# rev0_1_parts_placement.net
KiCad netlist of a schematic drawn in EAGLE
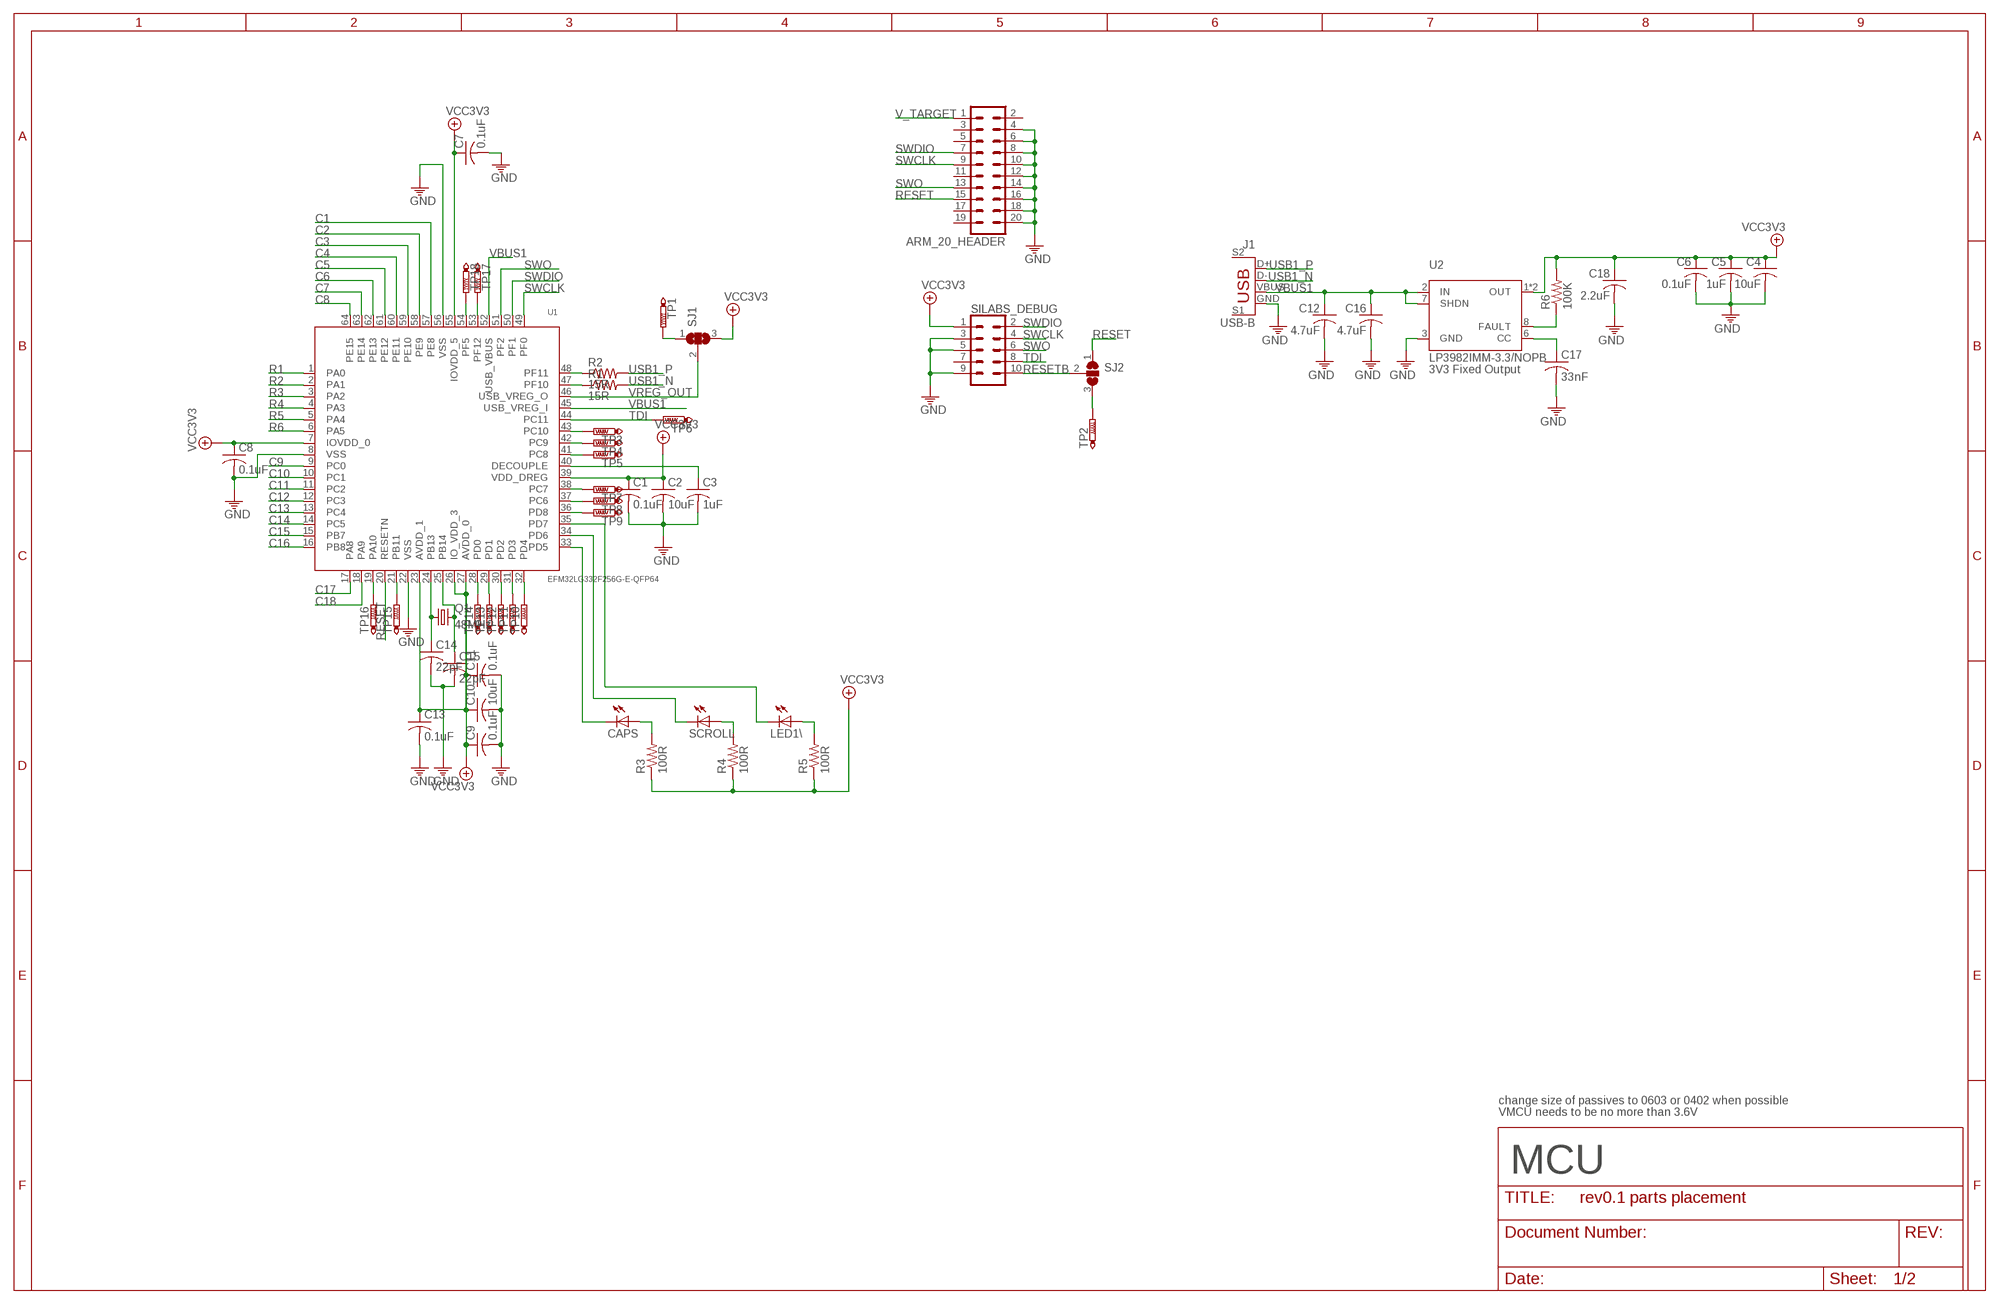
[diagram p0: schematic, sheet 1]
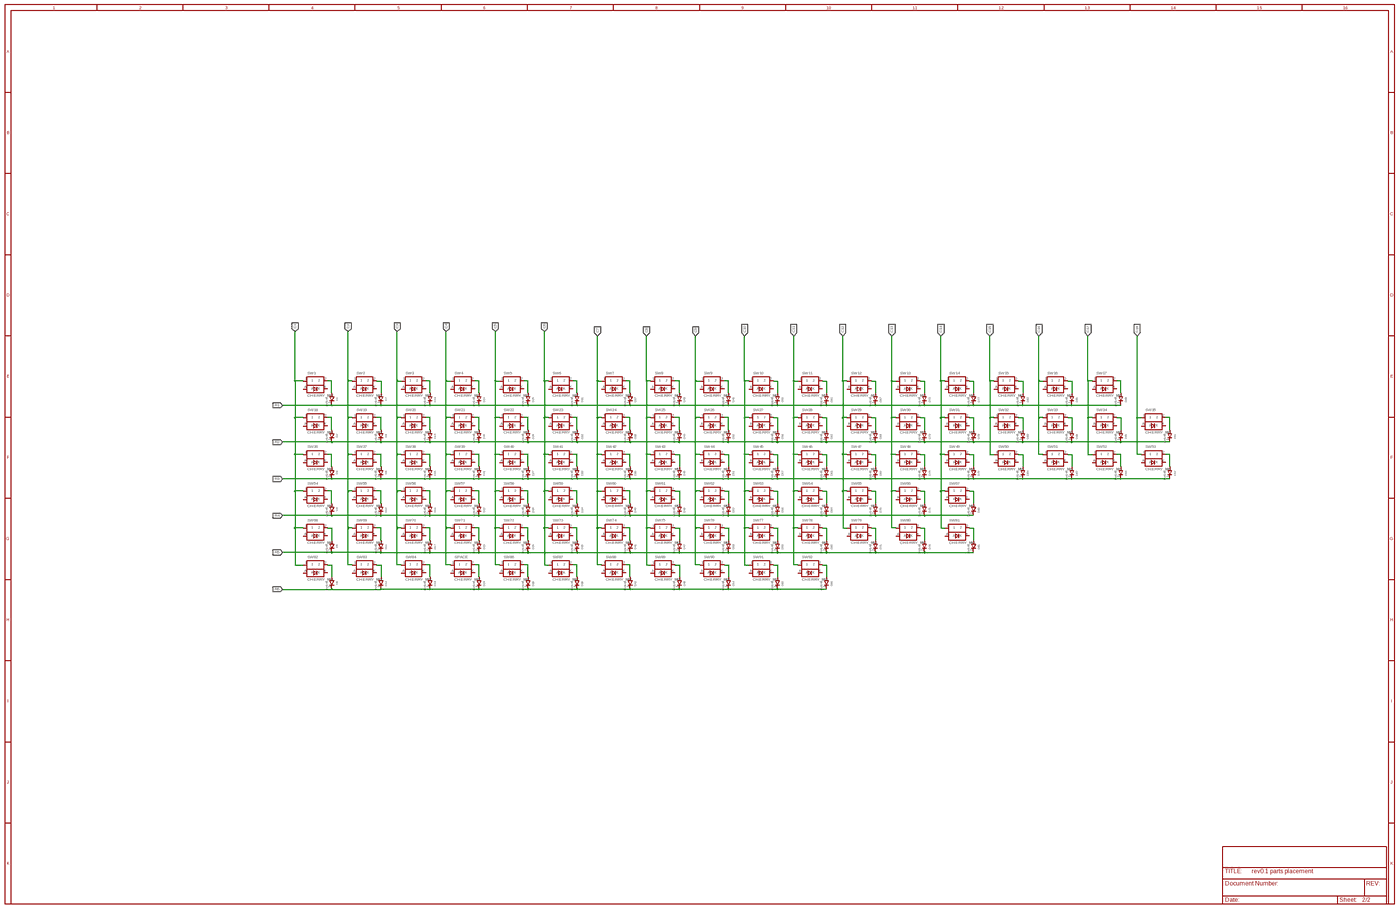
[diagram p1: schematic, sheet 2, overview]
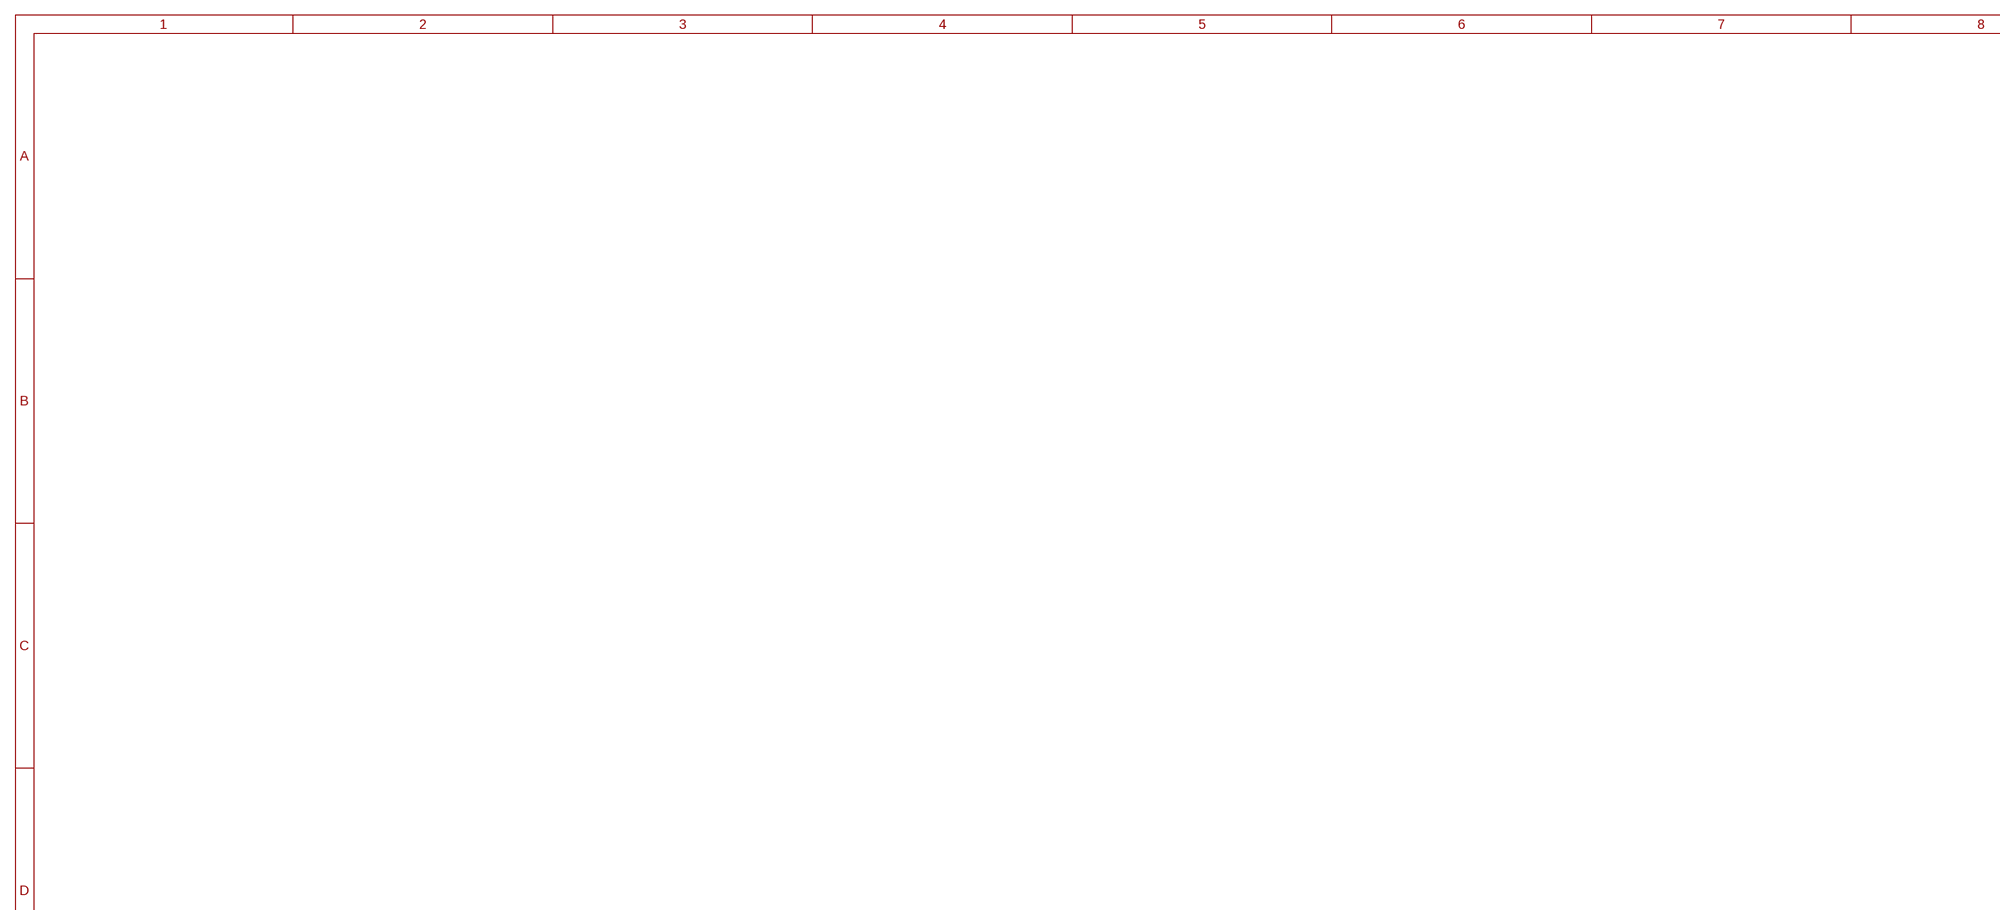
[diagram p2: schematic, sheet 2, part 1 of 4]
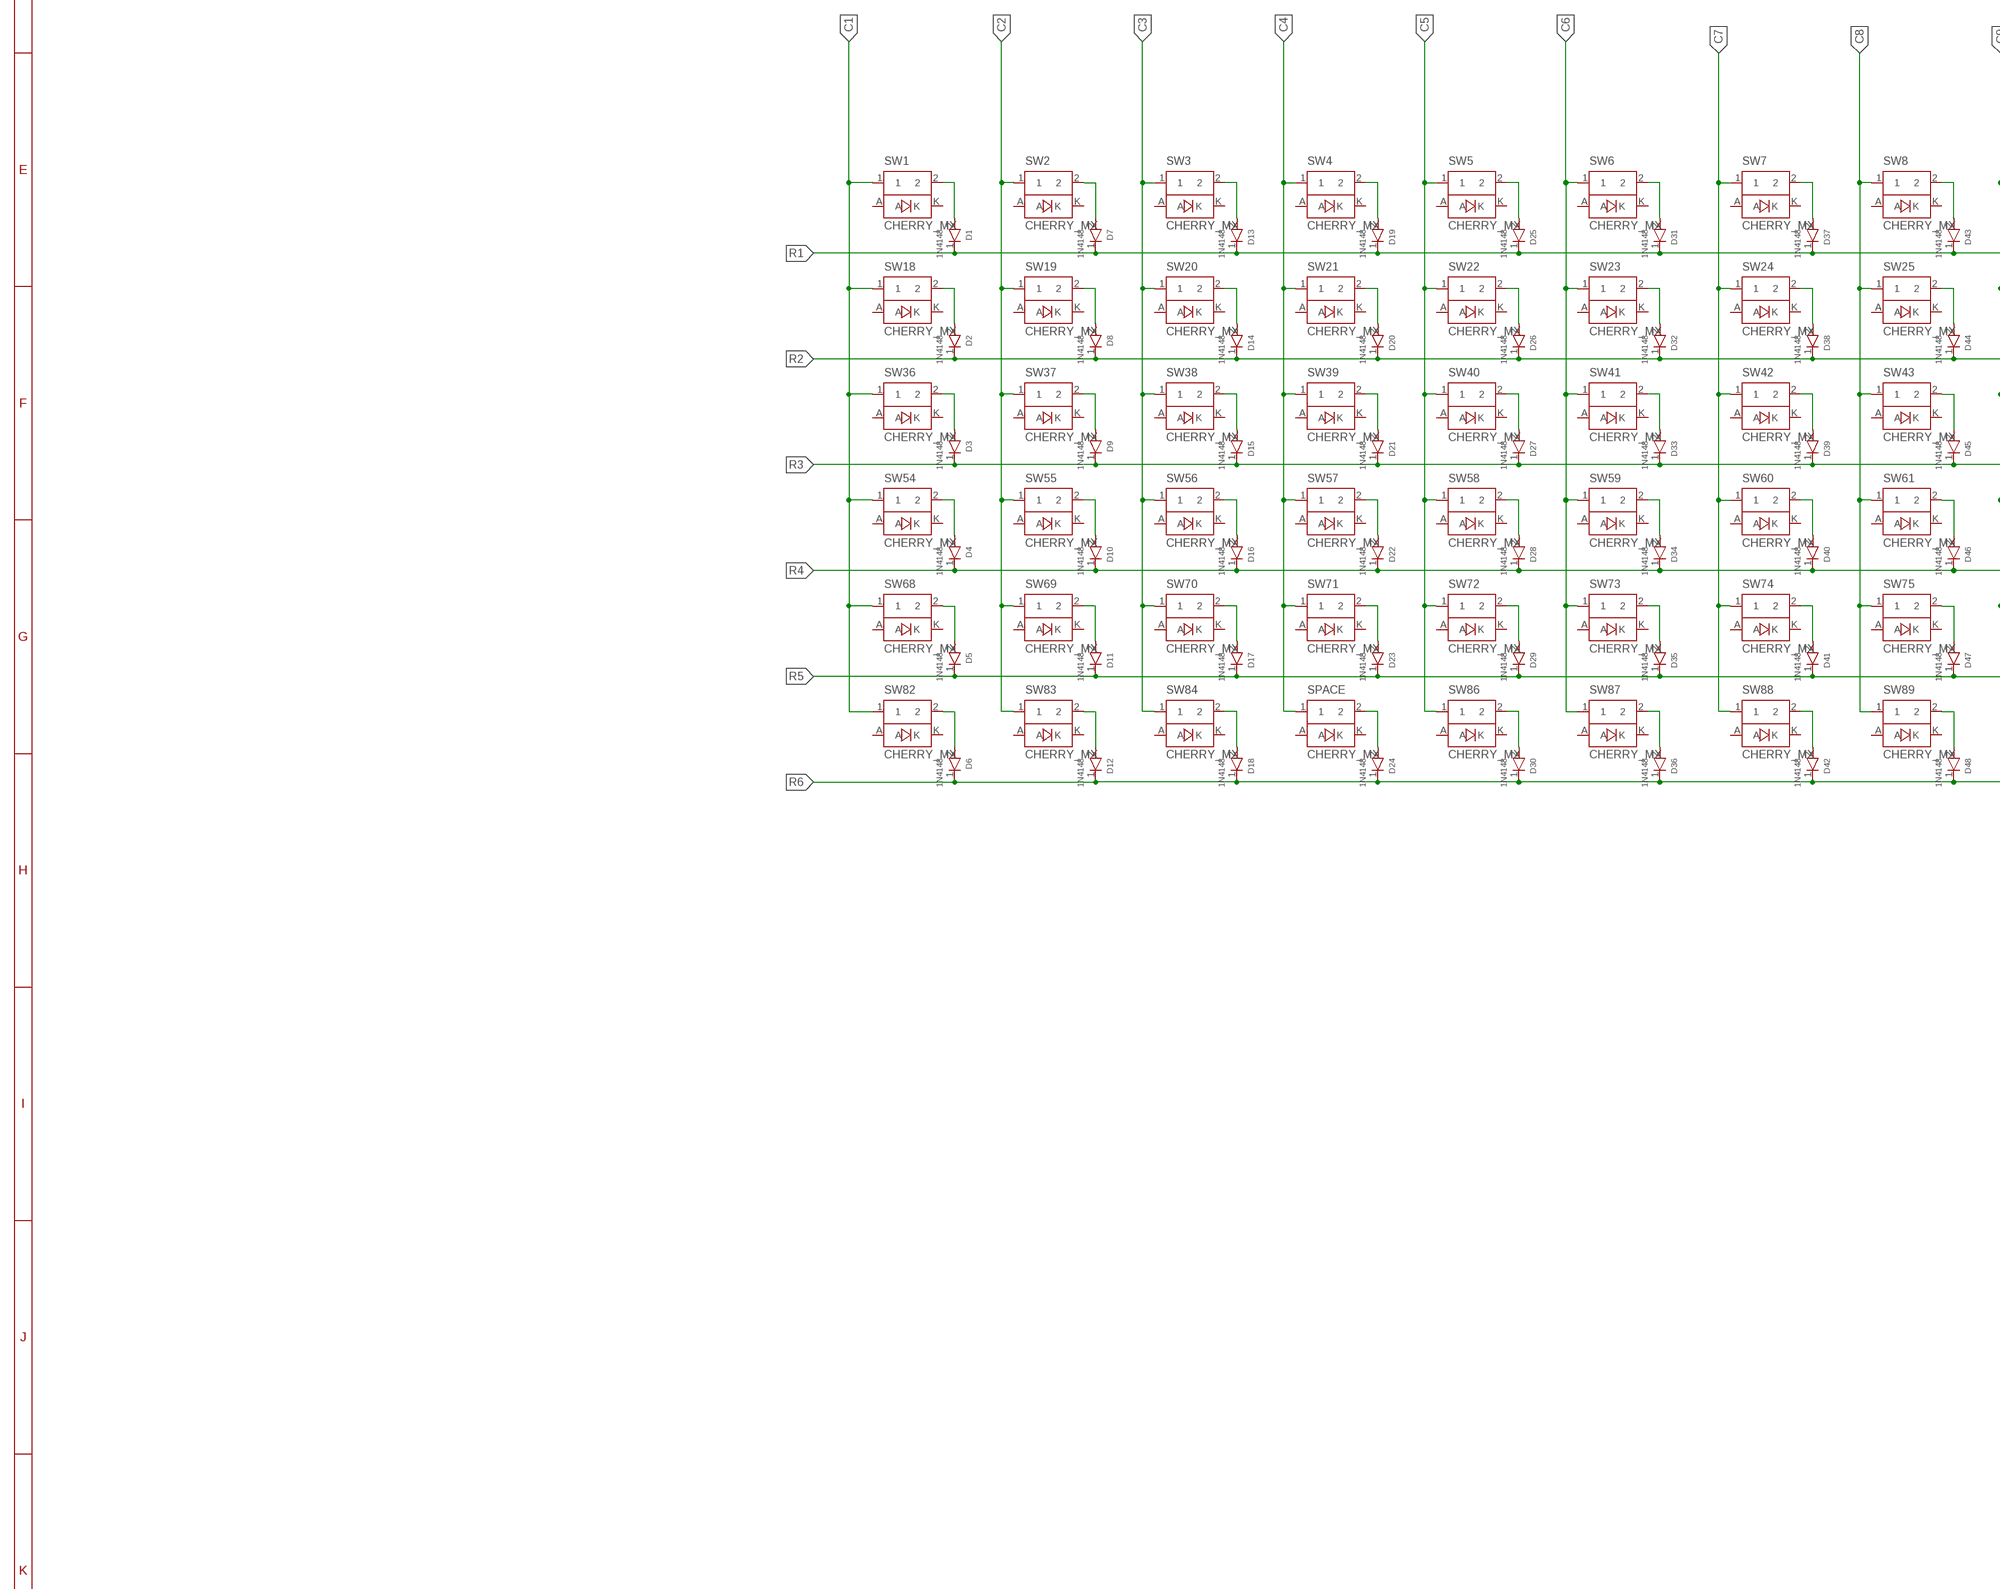
[diagram p3: schematic, sheet 2, part 2 of 4]
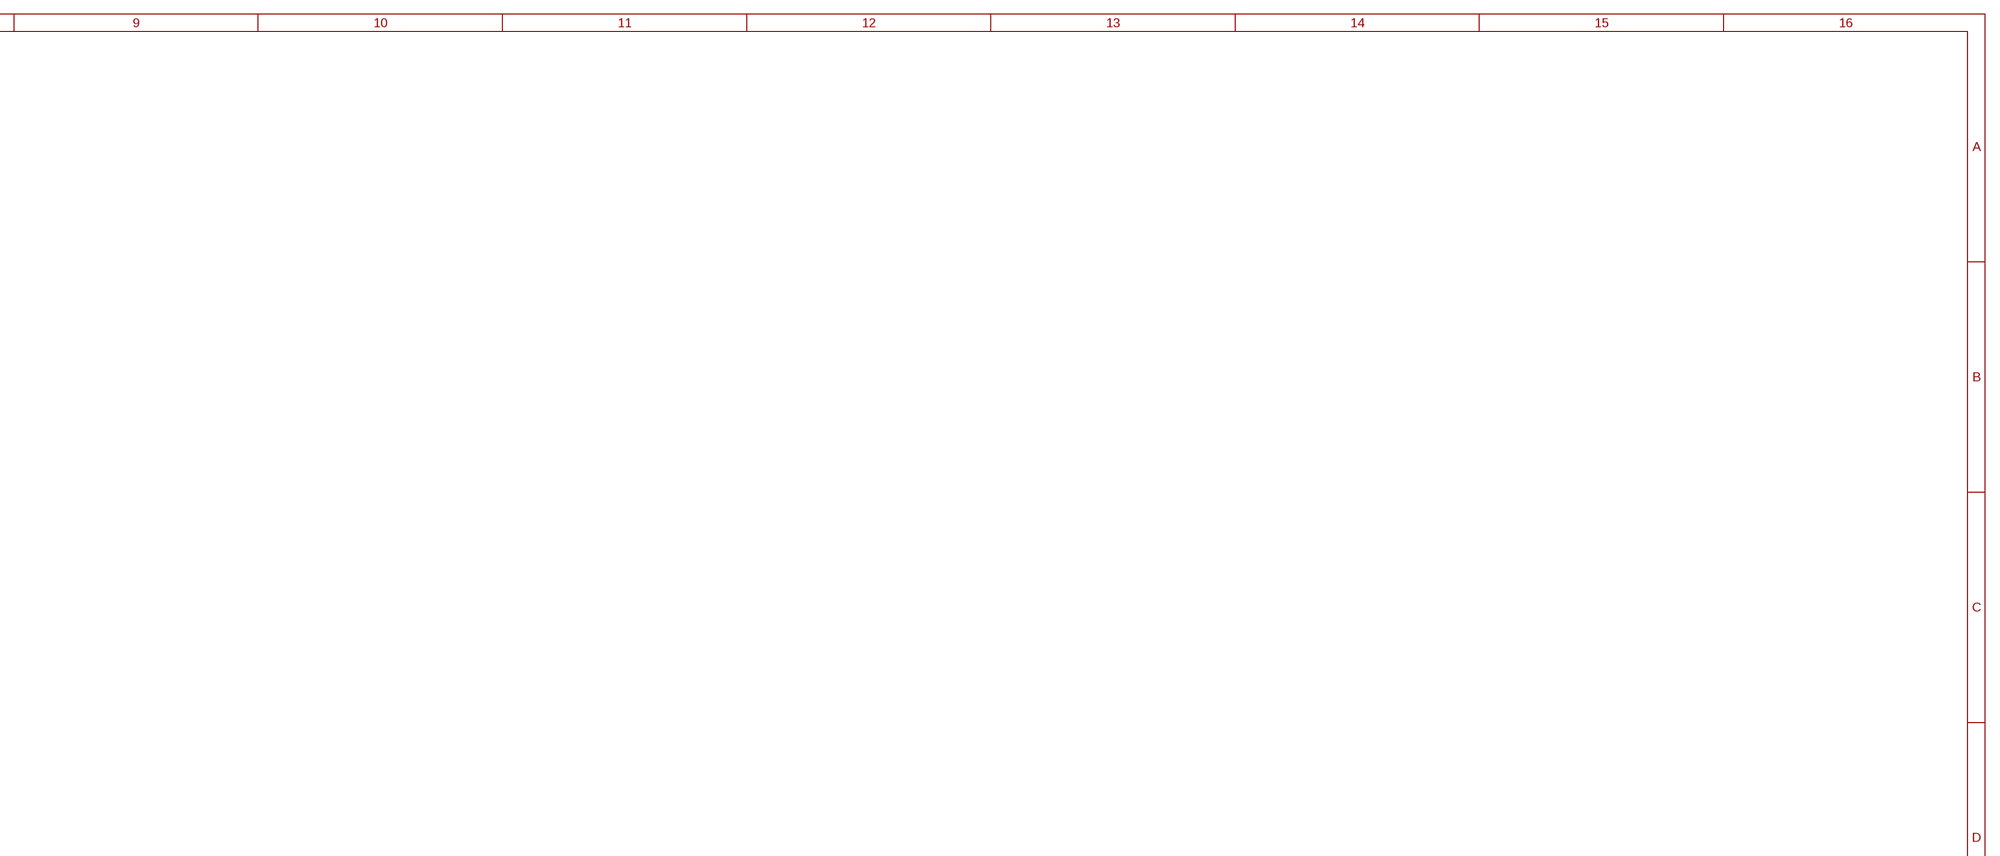
[diagram p4: schematic, sheet 2, part 3 of 4]
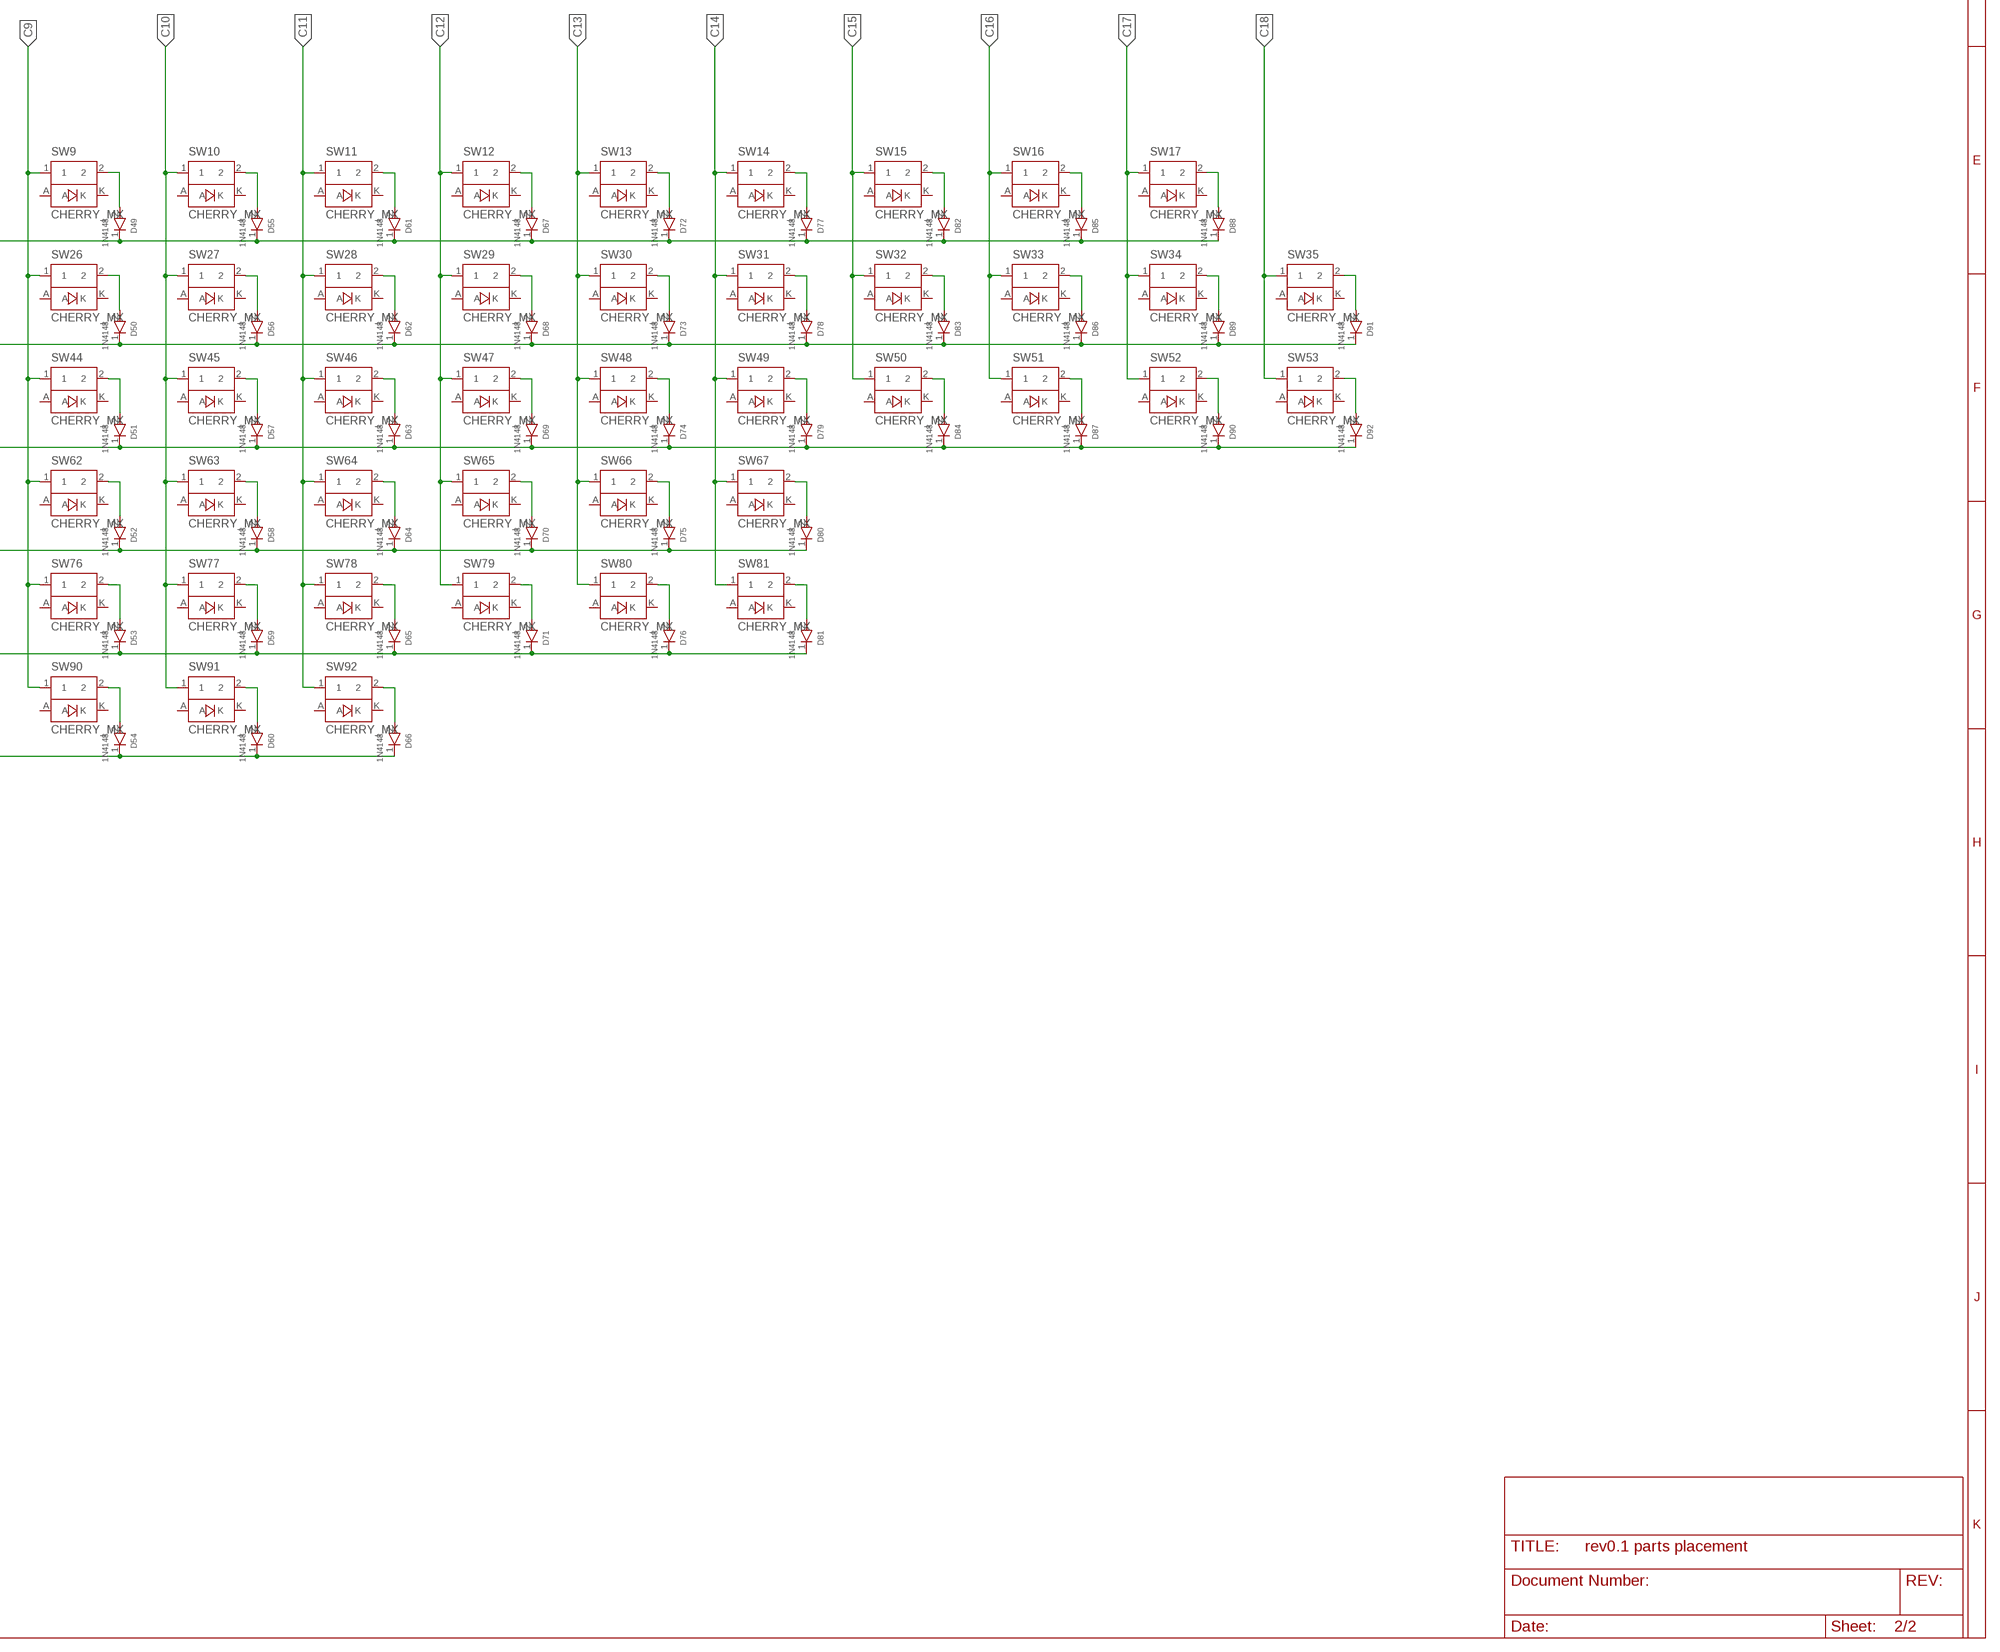
[diagram p5: schematic, sheet 2, part 4 of 4]

(export (version "E")
  (design (tool "Eeschema 10.0.6"))
  (components
    (comp (ref "ARM_20_HEADER")
      (value "MA10-2")
      (footprint "eagle-import:MA10-2")
      (libsource (lib "eagle-import") (part "MA10-2"))
    )
    (comp (ref "C1")
      (value "0.1uF")
      (footprint "eagle-import:C0402")
      (libsource (lib "eagle-import") (part "C-USC0402"))
    )
    (comp (ref "C2")
      (value "10uF")
      (footprint "eagle-import:C0805")
      (libsource (lib "eagle-import") (part "C-USC0805"))
    )
    (comp (ref "C3")
      (value "1uF")
      (footprint "eagle-import:C0402")
      (libsource (lib "eagle-import") (part "C-USC0402"))
    )
    (comp (ref "C4")
      (value "10uF")
      (footprint "eagle-import:C0805")
      (libsource (lib "eagle-import") (part "C-USC0805"))
    )
    (comp (ref "C5")
      (value "1uF")
      (footprint "eagle-import:C0402")
      (libsource (lib "eagle-import") (part "C-USC0402"))
    )
    (comp (ref "C6")
      (value "0.1uF")
      (footprint "eagle-import:C0402")
      (libsource (lib "eagle-import") (part "C-USC0402"))
    )
    (comp (ref "C7")
      (value "0.1uF")
      (footprint "eagle-import:C0402")
      (libsource (lib "eagle-import") (part "C-USC0402"))
    )
    (comp (ref "C8")
      (value "0.1uF")
      (footprint "eagle-import:C0402")
      (libsource (lib "eagle-import") (part "C-USC0402"))
    )
    (comp (ref "C9")
      (value "0.1uF")
      (footprint "eagle-import:C0402")
      (libsource (lib "eagle-import") (part "C-USC0402"))
    )
    (comp (ref "C10")
      (value "10uF")
      (footprint "eagle-import:C0805")
      (libsource (lib "eagle-import") (part "C-USC0805"))
    )
    (comp (ref "C11")
      (value "0.1uF")
      (footprint "eagle-import:C0402")
      (libsource (lib "eagle-import") (part "C-USC0402"))
    )
    (comp (ref "C12")
      (value "4.7uF")
      (footprint "eagle-import:C0805")
      (libsource (lib "eagle-import") (part "C-USC0805"))
    )
    (comp (ref "C13")
      (value "0.1uF")
      (footprint "eagle-import:C0402")
      (libsource (lib "eagle-import") (part "C-USC0402"))
    )
    (comp (ref "C14")
      (value "22pF")
      (footprint "eagle-import:C0402")
      (libsource (lib "eagle-import") (part "C-USC0402"))
    )
    (comp (ref "C15")
      (value "22pF")
      (footprint "eagle-import:C0402")
      (libsource (lib "eagle-import") (part "C-USC0402"))
    )
    (comp (ref "C16")
      (value "4.7uF")
      (footprint "eagle-import:C0805")
      (libsource (lib "eagle-import") (part "C-USC0805"))
    )
    (comp (ref "C17")
      (value "33nF")
      (footprint "eagle-import:C0402")
      (libsource (lib "eagle-import") (part "C-USC0402"))
    )
    (comp (ref "C18")
      (value "2.2uF")
      (footprint "eagle-import:C0805")
      (libsource (lib "eagle-import") (part "C-USC0805"))
    )
    (comp (ref "CAPS")
      (value "LEDCHIP-LED0805")
      (footprint "eagle-import:CHIP-LED0805")
      (libsource (lib "eagle-import") (part "LEDCHIP-LED0805"))
    )
    (comp (ref "J1")
      (value "USB-B")
      (footprint "eagle-import:USB-B-PTH")
      (libsource (lib "eagle-import") (part "USBPTH"))
    )
    (comp (ref "LED1\\")
      (value "LEDCHIP-LED0805")
      (footprint "eagle-import:CHIP-LED0805")
      (libsource (lib "eagle-import") (part "LEDCHIP-LED0805"))
    )
    (comp (ref "Q1")
      (value "48MHz")
      (footprint "eagle-import:CTS406")
      (libsource (lib "eagle-import") (part "CRYSTALCTS406"))
    )
    (comp (ref "R1")
      (value "15R")
      (footprint "eagle-import:R0402")
      (libsource (lib "eagle-import") (part "R-US_R0402"))
    )
    (comp (ref "R2")
      (value "15R")
      (footprint "eagle-import:R0402")
      (libsource (lib "eagle-import") (part "R-US_R0402"))
    )
    (comp (ref "R3")
      (value "100R")
      (footprint "eagle-import:R0402")
      (libsource (lib "eagle-import") (part "R-US_R0402"))
    )
    (comp (ref "R4")
      (value "100R")
      (footprint "eagle-import:R0402")
      (libsource (lib "eagle-import") (part "R-US_R0402"))
    )
    (comp (ref "R5")
      (value "100R")
      (footprint "eagle-import:R0402")
      (libsource (lib "eagle-import") (part "R-US_R0402"))
    )
    (comp (ref "R6")
      (value "100K")
      (footprint "eagle-import:R0402")
      (libsource (lib "eagle-import") (part "R-US_R0402"))
    )
    (comp (ref "SCROLL")
      (value "LEDCHIP-LED0805")
      (footprint "eagle-import:CHIP-LED0805")
      (libsource (lib "eagle-import") (part "LEDCHIP-LED0805"))
    )
    (comp (ref "SILABS_DEBUG")
      (value "CONN_05X2SHD_LOCK")
      (footprint "eagle-import:2X5-SHROUDED_LOCK")
      (libsource (lib "eagle-import") (part "CONN_05X2SHD_LOCK"))
    )
    (comp (ref "SJ1")
      (value "SJ2W")
      (footprint "eagle-import:SJ_2")
      (libsource (lib "eagle-import") (part "SJ2W"))
    )
    (comp (ref "SJ2")
      (value "SJ2W")
      (footprint "eagle-import:SJ_2")
      (libsource (lib "eagle-import") (part "SJ2W"))
    )
    (comp (ref "TP1")
      (value "PTR1B2,54")
      (footprint "eagle-import:B2,54")
      (libsource (lib "eagle-import") (part "PTR1B2,54"))
    )
    (comp (ref "TP2")
      (value "PTR1B2,54")
      (footprint "eagle-import:B2,54")
      (libsource (lib "eagle-import") (part "PTR1B2,54"))
    )
    (comp (ref "TP3")
      (value "PTR1B1,27")
      (footprint "eagle-import:B1,27")
      (libsource (lib "eagle-import") (part "PTR1B1,27"))
    )
    (comp (ref "TP4")
      (value "PTR1B1,27")
      (footprint "eagle-import:B1,27")
      (libsource (lib "eagle-import") (part "PTR1B1,27"))
    )
    (comp (ref "TP5")
      (value "PTR1B1,27")
      (footprint "eagle-import:B1,27")
      (libsource (lib "eagle-import") (part "PTR1B1,27"))
    )
    (comp (ref "TP6")
      (value "PTR1B1,27")
      (footprint "eagle-import:B1,27")
      (libsource (lib "eagle-import") (part "PTR1B1,27"))
    )
    (comp (ref "TP7")
      (value "PTR1B1,27")
      (footprint "eagle-import:B1,27")
      (libsource (lib "eagle-import") (part "PTR1B1,27"))
    )
    (comp (ref "TP8")
      (value "PTR1B1,27")
      (footprint "eagle-import:B1,27")
      (libsource (lib "eagle-import") (part "PTR1B1,27"))
    )
    (comp (ref "TP9")
      (value "PTR1B1,27")
      (footprint "eagle-import:B1,27")
      (libsource (lib "eagle-import") (part "PTR1B1,27"))
    )
    (comp (ref "TP10")
      (value "PTR1B1,27")
      (footprint "eagle-import:B1,27")
      (libsource (lib "eagle-import") (part "PTR1B1,27"))
    )
    (comp (ref "TP11")
      (value "PTR1B1,27")
      (footprint "eagle-import:B1,27")
      (libsource (lib "eagle-import") (part "PTR1B1,27"))
    )
    (comp (ref "TP12")
      (value "PTR1B1,27")
      (footprint "eagle-import:B1,27")
      (libsource (lib "eagle-import") (part "PTR1B1,27"))
    )
    (comp (ref "TP13")
      (value "PTR1B1,27")
      (footprint "eagle-import:B1,27")
      (libsource (lib "eagle-import") (part "PTR1B1,27"))
    )
    (comp (ref "TP14")
      (value "PTR1B1,27")
      (footprint "eagle-import:B1,27")
      (libsource (lib "eagle-import") (part "PTR1B1,27"))
    )
    (comp (ref "TP15")
      (value "PTR1B1,27")
      (footprint "eagle-import:B1,27")
      (libsource (lib "eagle-import") (part "PTR1B1,27"))
    )
    (comp (ref "TP16")
      (value "PTR1B1,27")
      (footprint "eagle-import:B1,27")
      (libsource (lib "eagle-import") (part "PTR1B1,27"))
    )
    (comp (ref "TP17")
      (value "PTR1B1,27")
      (footprint "eagle-import:B1,27")
      (libsource (lib "eagle-import") (part "PTR1B1,27"))
    )
    (comp (ref "TP18")
      (value "PTR1B1,27")
      (footprint "eagle-import:B1,27")
      (libsource (lib "eagle-import") (part "PTR1B1,27"))
    )
    (comp (ref "U1")
      (value "EFM32LG332F256G-E-QFP64")
      (footprint "eagle-import:EFM32LG332F256G-E-QFP64")
      (libsource (lib "eagle-import") (part "EFM32LG332F256G-E-QFP64"))
    )
    (comp (ref "U2")
      (value "LP3982IMM-3.3/NOPB")
      (footprint "eagle-import:LP3982IMM-3.3_NOPB")
      (libsource (lib "eagle-import") (part "LP3982IMM-3.3/NOPB"))
    )
    (comp (ref "D1")
      (value "1N4148")
      (footprint "eagle-import:SOD323")
      (libsource (lib "eagle-import") (part "1N4148"))
    )
    (comp (ref "D2")
      (value "1N4148")
      (footprint "eagle-import:SOD323")
      (libsource (lib "eagle-import") (part "1N4148"))
    )
    (comp (ref "D3")
      (value "1N4148")
      (footprint "eagle-import:SOD323")
      (libsource (lib "eagle-import") (part "1N4148"))
    )
    (comp (ref "D4")
      (value "1N4148")
      (footprint "eagle-import:SOD323")
      (libsource (lib "eagle-import") (part "1N4148"))
    )
    (comp (ref "D5")
      (value "1N4148")
      (footprint "eagle-import:SOD323")
      (libsource (lib "eagle-import") (part "1N4148"))
    )
    (comp (ref "D6")
      (value "1N4148")
      (footprint "eagle-import:SOD323")
      (libsource (lib "eagle-import") (part "1N4148"))
    )
    (comp (ref "D7")
      (value "1N4148")
      (footprint "eagle-import:SOD323")
      (libsource (lib "eagle-import") (part "1N4148"))
    )
    (comp (ref "D8")
      (value "1N4148")
      (footprint "eagle-import:SOD323")
      (libsource (lib "eagle-import") (part "1N4148"))
    )
    (comp (ref "D9")
      (value "1N4148")
      (footprint "eagle-import:SOD323")
      (libsource (lib "eagle-import") (part "1N4148"))
    )
    (comp (ref "D10")
      (value "1N4148")
      (footprint "eagle-import:SOD323")
      (libsource (lib "eagle-import") (part "1N4148"))
    )
    (comp (ref "D11")
      (value "1N4148")
      (footprint "eagle-import:SOD323")
      (libsource (lib "eagle-import") (part "1N4148"))
    )
    (comp (ref "D12")
      (value "1N4148")
      (footprint "eagle-import:SOD323")
      (libsource (lib "eagle-import") (part "1N4148"))
    )
    (comp (ref "D13")
      (value "1N4148")
      (footprint "eagle-import:SOD323")
      (libsource (lib "eagle-import") (part "1N4148"))
    )
    (comp (ref "D14")
      (value "1N4148")
      (footprint "eagle-import:SOD323")
      (libsource (lib "eagle-import") (part "1N4148"))
    )
    (comp (ref "D15")
      (value "1N4148")
      (footprint "eagle-import:SOD323")
      (libsource (lib "eagle-import") (part "1N4148"))
    )
    (comp (ref "D16")
      (value "1N4148")
      (footprint "eagle-import:SOD323")
      (libsource (lib "eagle-import") (part "1N4148"))
    )
    (comp (ref "D17")
      (value "1N4148")
      (footprint "eagle-import:SOD323")
      (libsource (lib "eagle-import") (part "1N4148"))
    )
    (comp (ref "D18")
      (value "1N4148")
      (footprint "eagle-import:SOD323")
      (libsource (lib "eagle-import") (part "1N4148"))
    )
    (comp (ref "D19")
      (value "1N4148")
      (footprint "eagle-import:SOD323")
      (libsource (lib "eagle-import") (part "1N4148"))
    )
    (comp (ref "D20")
      (value "1N4148")
      (footprint "eagle-import:SOD323")
      (libsource (lib "eagle-import") (part "1N4148"))
    )
    (comp (ref "D21")
      (value "1N4148")
      (footprint "eagle-import:SOD323")
      (libsource (lib "eagle-import") (part "1N4148"))
    )
    (comp (ref "D22")
      (value "1N4148")
      (footprint "eagle-import:SOD323")
      (libsource (lib "eagle-import") (part "1N4148"))
    )
    (comp (ref "D23")
      (value "1N4148")
      (footprint "eagle-import:SOD323")
      (libsource (lib "eagle-import") (part "1N4148"))
    )
    (comp (ref "D24")
      (value "1N4148")
      (footprint "eagle-import:SOD323")
      (libsource (lib "eagle-import") (part "1N4148"))
    )
    (comp (ref "D25")
      (value "1N4148")
      (footprint "eagle-import:SOD323")
      (libsource (lib "eagle-import") (part "1N4148"))
    )
    (comp (ref "D26")
      (value "1N4148")
      (footprint "eagle-import:SOD323")
      (libsource (lib "eagle-import") (part "1N4148"))
    )
    (comp (ref "D27")
      (value "1N4148")
      (footprint "eagle-import:SOD323")
      (libsource (lib "eagle-import") (part "1N4148"))
    )
    (comp (ref "D28")
      (value "1N4148")
      (footprint "eagle-import:SOD323")
      (libsource (lib "eagle-import") (part "1N4148"))
    )
    (comp (ref "D29")
      (value "1N4148")
      (footprint "eagle-import:SOD323")
      (libsource (lib "eagle-import") (part "1N4148"))
    )
    (comp (ref "D30")
      (value "1N4148")
      (footprint "eagle-import:SOD323")
      (libsource (lib "eagle-import") (part "1N4148"))
    )
    (comp (ref "D31")
      (value "1N4148")
      (footprint "eagle-import:SOD323")
      (libsource (lib "eagle-import") (part "1N4148"))
    )
    (comp (ref "D32")
      (value "1N4148")
      (footprint "eagle-import:SOD323")
      (libsource (lib "eagle-import") (part "1N4148"))
    )
    (comp (ref "D33")
      (value "1N4148")
      (footprint "eagle-import:SOD323")
      (libsource (lib "eagle-import") (part "1N4148"))
    )
    (comp (ref "D34")
      (value "1N4148")
      (footprint "eagle-import:SOD323")
      (libsource (lib "eagle-import") (part "1N4148"))
    )
    (comp (ref "D35")
      (value "1N4148")
      (footprint "eagle-import:SOD323")
      (libsource (lib "eagle-import") (part "1N4148"))
    )
    (comp (ref "D36")
      (value "1N4148")
      (footprint "eagle-import:SOD323")
      (libsource (lib "eagle-import") (part "1N4148"))
    )
    (comp (ref "D37")
      (value "1N4148")
      (footprint "eagle-import:SOD323")
      (libsource (lib "eagle-import") (part "1N4148"))
    )
    (comp (ref "D38")
      (value "1N4148")
      (footprint "eagle-import:SOD323")
      (libsource (lib "eagle-import") (part "1N4148"))
    )
    (comp (ref "D39")
      (value "1N4148")
      (footprint "eagle-import:SOD323")
      (libsource (lib "eagle-import") (part "1N4148"))
    )
    (comp (ref "D40")
      (value "1N4148")
      (footprint "eagle-import:SOD323")
      (libsource (lib "eagle-import") (part "1N4148"))
    )
    (comp (ref "D41")
      (value "1N4148")
      (footprint "eagle-import:SOD323")
      (libsource (lib "eagle-import") (part "1N4148"))
    )
    (comp (ref "D42")
      (value "1N4148")
      (footprint "eagle-import:SOD323")
      (libsource (lib "eagle-import") (part "1N4148"))
    )
    (comp (ref "D43")
      (value "1N4148")
      (footprint "eagle-import:SOD323")
      (libsource (lib "eagle-import") (part "1N4148"))
    )
    (comp (ref "D44")
      (value "1N4148")
      (footprint "eagle-import:SOD323")
      (libsource (lib "eagle-import") (part "1N4148"))
    )
    (comp (ref "D45")
      (value "1N4148")
      (footprint "eagle-import:SOD323")
      (libsource (lib "eagle-import") (part "1N4148"))
    )
    (comp (ref "D46")
      (value "1N4148")
      (footprint "eagle-import:SOD323")
      (libsource (lib "eagle-import") (part "1N4148"))
    )
    (comp (ref "D47")
      (value "1N4148")
      (footprint "eagle-import:SOD323")
      (libsource (lib "eagle-import") (part "1N4148"))
    )
    (comp (ref "D48")
      (value "1N4148")
      (footprint "eagle-import:SOD323")
      (libsource (lib "eagle-import") (part "1N4148"))
    )
    (comp (ref "D49")
      (value "1N4148")
      (footprint "eagle-import:SOD323")
      (libsource (lib "eagle-import") (part "1N4148"))
    )
    (comp (ref "D50")
      (value "1N4148")
      (footprint "eagle-import:SOD323")
      (libsource (lib "eagle-import") (part "1N4148"))
    )
    (comp (ref "D51")
      (value "1N4148")
      (footprint "eagle-import:SOD323")
      (libsource (lib "eagle-import") (part "1N4148"))
    )
    (comp (ref "D52")
      (value "1N4148")
      (footprint "eagle-import:SOD323")
      (libsource (lib "eagle-import") (part "1N4148"))
    )
    (comp (ref "D53")
      (value "1N4148")
      (footprint "eagle-import:SOD323")
      (libsource (lib "eagle-import") (part "1N4148"))
    )
    (comp (ref "D54")
      (value "1N4148")
      (footprint "eagle-import:SOD323")
      (libsource (lib "eagle-import") (part "1N4148"))
    )
    (comp (ref "D55")
      (value "1N4148")
      (footprint "eagle-import:SOD323")
      (libsource (lib "eagle-import") (part "1N4148"))
    )
    (comp (ref "D56")
      (value "1N4148")
      (footprint "eagle-import:SOD323")
      (libsource (lib "eagle-import") (part "1N4148"))
    )
    (comp (ref "D57")
      (value "1N4148")
      (footprint "eagle-import:SOD323")
      (libsource (lib "eagle-import") (part "1N4148"))
    )
    (comp (ref "D58")
      (value "1N4148")
      (footprint "eagle-import:SOD323")
      (libsource (lib "eagle-import") (part "1N4148"))
    )
    (comp (ref "D59")
      (value "1N4148")
      (footprint "eagle-import:SOD323")
      (libsource (lib "eagle-import") (part "1N4148"))
    )
    (comp (ref "D60")
      (value "1N4148")
      (footprint "eagle-import:SOD323")
      (libsource (lib "eagle-import") (part "1N4148"))
    )
    (comp (ref "D61")
      (value "1N4148")
      (footprint "eagle-import:SOD323")
      (libsource (lib "eagle-import") (part "1N4148"))
    )
    (comp (ref "D62")
      (value "1N4148")
      (footprint "eagle-import:SOD323")
      (libsource (lib "eagle-import") (part "1N4148"))
    )
    (comp (ref "D63")
      (value "1N4148")
      (footprint "eagle-import:SOD323")
      (libsource (lib "eagle-import") (part "1N4148"))
    )
    (comp (ref "D64")
      (value "1N4148")
      (footprint "eagle-import:SOD323")
      (libsource (lib "eagle-import") (part "1N4148"))
    )
    (comp (ref "D65")
      (value "1N4148")
      (footprint "eagle-import:SOD323")
      (libsource (lib "eagle-import") (part "1N4148"))
    )
    (comp (ref "D66")
      (value "1N4148")
      (footprint "eagle-import:SOD323")
      (libsource (lib "eagle-import") (part "1N4148"))
    )
    (comp (ref "D67")
      (value "1N4148")
      (footprint "eagle-import:SOD323")
      (libsource (lib "eagle-import") (part "1N4148"))
    )
    (comp (ref "D68")
      (value "1N4148")
      (footprint "eagle-import:SOD323")
      (libsource (lib "eagle-import") (part "1N4148"))
    )
    (comp (ref "D69")
      (value "1N4148")
      (footprint "eagle-import:SOD323")
      (libsource (lib "eagle-import") (part "1N4148"))
    )
    (comp (ref "D70")
      (value "1N4148")
      (footprint "eagle-import:SOD323")
      (libsource (lib "eagle-import") (part "1N4148"))
    )
    (comp (ref "D71")
      (value "1N4148")
      (footprint "eagle-import:SOD323")
      (libsource (lib "eagle-import") (part "1N4148"))
    )
    (comp (ref "D72")
      (value "1N4148")
      (footprint "eagle-import:SOD323")
      (libsource (lib "eagle-import") (part "1N4148"))
    )
    (comp (ref "D73")
      (value "1N4148")
      (footprint "eagle-import:SOD323")
      (libsource (lib "eagle-import") (part "1N4148"))
    )
    (comp (ref "D74")
      (value "1N4148")
      (footprint "eagle-import:SOD323")
      (libsource (lib "eagle-import") (part "1N4148"))
    )
    (comp (ref "D75")
      (value "1N4148")
      (footprint "eagle-import:SOD323")
      (libsource (lib "eagle-import") (part "1N4148"))
    )
    (comp (ref "D76")
      (value "1N4148")
      (footprint "eagle-import:SOD323")
      (libsource (lib "eagle-import") (part "1N4148"))
    )
    (comp (ref "D77")
      (value "1N4148")
      (footprint "eagle-import:SOD323")
      (libsource (lib "eagle-import") (part "1N4148"))
    )
    (comp (ref "D78")
      (value "1N4148")
      (footprint "eagle-import:SOD323")
      (libsource (lib "eagle-import") (part "1N4148"))
    )
    (comp (ref "D79")
      (value "1N4148")
      (footprint "eagle-import:SOD323")
      (libsource (lib "eagle-import") (part "1N4148"))
    )
    (comp (ref "D80")
      (value "1N4148")
      (footprint "eagle-import:SOD323")
      (libsource (lib "eagle-import") (part "1N4148"))
    )
    (comp (ref "D81")
      (value "1N4148")
      (footprint "eagle-import:SOD323")
      (libsource (lib "eagle-import") (part "1N4148"))
    )
    (comp (ref "D82")
      (value "1N4148")
      (footprint "eagle-import:SOD323")
      (libsource (lib "eagle-import") (part "1N4148"))
    )
    (comp (ref "D83")
      (value "1N4148")
      (footprint "eagle-import:SOD323")
      (libsource (lib "eagle-import") (part "1N4148"))
    )
    (comp (ref "D84")
      (value "1N4148")
      (footprint "eagle-import:SOD323")
      (libsource (lib "eagle-import") (part "1N4148"))
    )
    (comp (ref "D85")
      (value "1N4148")
      (footprint "eagle-import:SOD323")
      (libsource (lib "eagle-import") (part "1N4148"))
    )
    (comp (ref "D86")
      (value "1N4148")
      (footprint "eagle-import:SOD323")
      (libsource (lib "eagle-import") (part "1N4148"))
    )
    (comp (ref "D87")
      (value "1N4148")
      (footprint "eagle-import:SOD323")
      (libsource (lib "eagle-import") (part "1N4148"))
    )
    (comp (ref "D88")
      (value "1N4148")
      (footprint "eagle-import:SOD323")
      (libsource (lib "eagle-import") (part "1N4148"))
    )
    (comp (ref "D89")
      (value "1N4148")
      (footprint "eagle-import:SOD323")
      (libsource (lib "eagle-import") (part "1N4148"))
    )
    (comp (ref "D90")
      (value "1N4148")
      (footprint "eagle-import:SOD323")
      (libsource (lib "eagle-import") (part "1N4148"))
    )
    (comp (ref "D91")
      (value "1N4148")
      (footprint "eagle-import:SOD323")
      (libsource (lib "eagle-import") (part "1N4148"))
    )
    (comp (ref "D92")
      (value "1N4148")
      (footprint "eagle-import:SOD323")
      (libsource (lib "eagle-import") (part "1N4148"))
    )
    (comp (ref "SPACE")
      (value "CHERRY_MX")
      (footprint "eagle-import:CHERRY_MX")
      (libsource (lib "eagle-import") (part "CHERRY_MX"))
    )
    (comp (ref "SW1")
      (value "CHERRY_MX")
      (footprint "eagle-import:CHERRY_MX")
      (libsource (lib "eagle-import") (part "CHERRY_MX"))
    )
    (comp (ref "SW2")
      (value "CHERRY_MX")
      (footprint "eagle-import:CHERRY_MX")
      (libsource (lib "eagle-import") (part "CHERRY_MX"))
    )
    (comp (ref "SW3")
      (value "CHERRY_MX")
      (footprint "eagle-import:CHERRY_MX")
      (libsource (lib "eagle-import") (part "CHERRY_MX"))
    )
    (comp (ref "SW4")
      (value "CHERRY_MX")
      (footprint "eagle-import:CHERRY_MX")
      (libsource (lib "eagle-import") (part "CHERRY_MX"))
    )
    (comp (ref "SW5")
      (value "CHERRY_MX")
      (footprint "eagle-import:CHERRY_MX")
      (libsource (lib "eagle-import") (part "CHERRY_MX"))
    )
    (comp (ref "SW6")
      (value "CHERRY_MX")
      (footprint "eagle-import:CHERRY_MX")
      (libsource (lib "eagle-import") (part "CHERRY_MX"))
    )
    (comp (ref "SW7")
      (value "CHERRY_MX")
      (footprint "eagle-import:CHERRY_MX")
      (libsource (lib "eagle-import") (part "CHERRY_MX"))
    )
    (comp (ref "SW8")
      (value "CHERRY_MX")
      (footprint "eagle-import:CHERRY_MX")
      (libsource (lib "eagle-import") (part "CHERRY_MX"))
    )
    (comp (ref "SW9")
      (value "CHERRY_MX")
      (footprint "eagle-import:CHERRY_MX")
      (libsource (lib "eagle-import") (part "CHERRY_MX"))
    )
    (comp (ref "SW10")
      (value "CHERRY_MX")
      (footprint "eagle-import:CHERRY_MX")
      (libsource (lib "eagle-import") (part "CHERRY_MX"))
    )
    (comp (ref "SW11")
      (value "CHERRY_MX")
      (footprint "eagle-import:CHERRY_MX")
      (libsource (lib "eagle-import") (part "CHERRY_MX"))
    )
    (comp (ref "SW12")
      (value "CHERRY_MX")
      (footprint "eagle-import:CHERRY_MX")
      (libsource (lib "eagle-import") (part "CHERRY_MX"))
    )
    (comp (ref "SW13")
      (value "CHERRY_MX")
      (footprint "eagle-import:CHERRY_MX")
      (libsource (lib "eagle-import") (part "CHERRY_MX"))
    )
    (comp (ref "SW14")
      (value "CHERRY_MX")
      (footprint "eagle-import:CHERRY_MX")
      (libsource (lib "eagle-import") (part "CHERRY_MX"))
    )
    (comp (ref "SW15")
      (value "CHERRY_MX")
      (footprint "eagle-import:CHERRY_MX")
      (libsource (lib "eagle-import") (part "CHERRY_MX"))
    )
    (comp (ref "SW16")
      (value "CHERRY_MX")
      (footprint "eagle-import:CHERRY_MX")
      (libsource (lib "eagle-import") (part "CHERRY_MX"))
    )
    (comp (ref "SW17")
      (value "CHERRY_MX")
      (footprint "eagle-import:CHERRY_MX")
      (libsource (lib "eagle-import") (part "CHERRY_MX"))
    )
    (comp (ref "SW18")
      (value "CHERRY_MX")
      (footprint "eagle-import:CHERRY_MX")
      (libsource (lib "eagle-import") (part "CHERRY_MX"))
    )
    (comp (ref "SW19")
      (value "CHERRY_MX")
      (footprint "eagle-import:CHERRY_MX")
      (libsource (lib "eagle-import") (part "CHERRY_MX"))
    )
    (comp (ref "SW20")
      (value "CHERRY_MX")
      (footprint "eagle-import:CHERRY_MX")
      (libsource (lib "eagle-import") (part "CHERRY_MX"))
    )
    (comp (ref "SW21")
      (value "CHERRY_MX")
      (footprint "eagle-import:CHERRY_MX")
      (libsource (lib "eagle-import") (part "CHERRY_MX"))
    )
    (comp (ref "SW22")
      (value "CHERRY_MX")
      (footprint "eagle-import:CHERRY_MX")
      (libsource (lib "eagle-import") (part "CHERRY_MX"))
    )
    (comp (ref "SW23")
      (value "CHERRY_MX")
      (footprint "eagle-import:CHERRY_MX")
      (libsource (lib "eagle-import") (part "CHERRY_MX"))
    )
    (comp (ref "SW24")
      (value "CHERRY_MX")
      (footprint "eagle-import:CHERRY_MX")
      (libsource (lib "eagle-import") (part "CHERRY_MX"))
    )
    (comp (ref "SW25")
      (value "CHERRY_MX")
      (footprint "eagle-import:CHERRY_MX")
      (libsource (lib "eagle-import") (part "CHERRY_MX"))
    )
    (comp (ref "SW26")
      (value "CHERRY_MX")
      (footprint "eagle-import:CHERRY_MX")
      (libsource (lib "eagle-import") (part "CHERRY_MX"))
    )
    (comp (ref "SW27")
      (value "CHERRY_MX")
      (footprint "eagle-import:CHERRY_MX")
      (libsource (lib "eagle-import") (part "CHERRY_MX"))
    )
    (comp (ref "SW28")
      (value "CHERRY_MX")
      (footprint "eagle-import:CHERRY_MX")
      (libsource (lib "eagle-import") (part "CHERRY_MX"))
    )
    (comp (ref "SW29")
      (value "CHERRY_MX")
      (footprint "eagle-import:CHERRY_MX")
      (libsource (lib "eagle-import") (part "CHERRY_MX"))
    )
    (comp (ref "SW30")
      (value "CHERRY_MX")
      (footprint "eagle-import:CHERRY_MX")
      (libsource (lib "eagle-import") (part "CHERRY_MX"))
    )
    (comp (ref "SW31")
      (value "CHERRY_MX")
      (footprint "eagle-import:CHERRY_MX")
      (libsource (lib "eagle-import") (part "CHERRY_MX"))
    )
    (comp (ref "SW32")
      (value "CHERRY_MX")
      (footprint "eagle-import:CHERRY_MX")
      (libsource (lib "eagle-import") (part "CHERRY_MX"))
    )
    (comp (ref "SW33")
      (value "CHERRY_MX")
      (footprint "eagle-import:CHERRY_MX")
      (libsource (lib "eagle-import") (part "CHERRY_MX"))
    )
    (comp (ref "SW34")
      (value "CHERRY_MX")
      (footprint "eagle-import:CHERRY_MX")
      (libsource (lib "eagle-import") (part "CHERRY_MX"))
    )
    (comp (ref "SW35")
      (value "CHERRY_MX")
      (footprint "eagle-import:CHERRY_MX")
      (libsource (lib "eagle-import") (part "CHERRY_MX"))
    )
    (comp (ref "SW36")
      (value "CHERRY_MX")
      (footprint "eagle-import:CHERRY_MX")
      (libsource (lib "eagle-import") (part "CHERRY_MX"))
    )
    (comp (ref "SW37")
      (value "CHERRY_MX")
      (footprint "eagle-import:CHERRY_MX")
      (libsource (lib "eagle-import") (part "CHERRY_MX"))
    )
    (comp (ref "SW38")
      (value "CHERRY_MX")
      (footprint "eagle-import:CHERRY_MX")
      (libsource (lib "eagle-import") (part "CHERRY_MX"))
    )
    (comp (ref "SW39")
      (value "CHERRY_MX")
      (footprint "eagle-import:CHERRY_MX")
      (libsource (lib "eagle-import") (part "CHERRY_MX"))
    )
    (comp (ref "SW40")
      (value "CHERRY_MX")
      (footprint "eagle-import:CHERRY_MX")
      (libsource (lib "eagle-import") (part "CHERRY_MX"))
    )
    (comp (ref "SW41")
      (value "CHERRY_MX")
      (footprint "eagle-import:CHERRY_MX")
      (libsource (lib "eagle-import") (part "CHERRY_MX"))
    )
    (comp (ref "SW42")
      (value "CHERRY_MX")
      (footprint "eagle-import:CHERRY_MX")
      (libsource (lib "eagle-import") (part "CHERRY_MX"))
    )
    (comp (ref "SW43")
      (value "CHERRY_MX")
      (footprint "eagle-import:CHERRY_MX")
      (libsource (lib "eagle-import") (part "CHERRY_MX"))
    )
    (comp (ref "SW44")
      (value "CHERRY_MX")
      (footprint "eagle-import:CHERRY_MX")
      (libsource (lib "eagle-import") (part "CHERRY_MX"))
    )
    (comp (ref "SW45")
      (value "CHERRY_MX")
      (footprint "eagle-import:CHERRY_MX")
      (libsource (lib "eagle-import") (part "CHERRY_MX"))
    )
    (comp (ref "SW46")
      (value "CHERRY_MX")
      (footprint "eagle-import:CHERRY_MX")
      (libsource (lib "eagle-import") (part "CHERRY_MX"))
    )
    (comp (ref "SW47")
      (value "CHERRY_MX")
      (footprint "eagle-import:CHERRY_MX")
      (libsource (lib "eagle-import") (part "CHERRY_MX"))
    )
    (comp (ref "SW48")
      (value "CHERRY_MX")
      (footprint "eagle-import:CHERRY_MX")
      (libsource (lib "eagle-import") (part "CHERRY_MX"))
    )
    (comp (ref "SW49")
      (value "CHERRY_MX")
      (footprint "eagle-import:CHERRY_MX")
      (libsource (lib "eagle-import") (part "CHERRY_MX"))
    )
    (comp (ref "SW50")
      (value "CHERRY_MX")
      (footprint "eagle-import:CHERRY_MX")
      (libsource (lib "eagle-import") (part "CHERRY_MX"))
    )
    (comp (ref "SW51")
      (value "CHERRY_MX")
      (footprint "eagle-import:CHERRY_MX")
      (libsource (lib "eagle-import") (part "CHERRY_MX"))
    )
    (comp (ref "SW52")
      (value "CHERRY_MX")
      (footprint "eagle-import:CHERRY_MX")
      (libsource (lib "eagle-import") (part "CHERRY_MX"))
    )
    (comp (ref "SW53")
      (value "CHERRY_MX")
      (footprint "eagle-import:CHERRY_MX")
      (libsource (lib "eagle-import") (part "CHERRY_MX"))
    )
    (comp (ref "SW54")
      (value "CHERRY_MX")
      (footprint "eagle-import:CHERRY_MX")
      (libsource (lib "eagle-import") (part "CHERRY_MX"))
    )
    (comp (ref "SW55")
      (value "CHERRY_MX")
      (footprint "eagle-import:CHERRY_MX")
      (libsource (lib "eagle-import") (part "CHERRY_MX"))
    )
    (comp (ref "SW56")
      (value "CHERRY_MX")
      (footprint "eagle-import:CHERRY_MX")
      (libsource (lib "eagle-import") (part "CHERRY_MX"))
    )
    (comp (ref "SW57")
      (value "CHERRY_MX")
      (footprint "eagle-import:CHERRY_MX")
      (libsource (lib "eagle-import") (part "CHERRY_MX"))
    )
    (comp (ref "SW58")
      (value "CHERRY_MX")
      (footprint "eagle-import:CHERRY_MX")
      (libsource (lib "eagle-import") (part "CHERRY_MX"))
    )
    (comp (ref "SW59")
      (value "CHERRY_MX")
      (footprint "eagle-import:CHERRY_MX")
      (libsource (lib "eagle-import") (part "CHERRY_MX"))
    )
    (comp (ref "SW60")
      (value "CHERRY_MX")
      (footprint "eagle-import:CHERRY_MX")
      (libsource (lib "eagle-import") (part "CHERRY_MX"))
    )
    (comp (ref "SW61")
      (value "CHERRY_MX")
      (footprint "eagle-import:CHERRY_MX")
      (libsource (lib "eagle-import") (part "CHERRY_MX"))
    )
    (comp (ref "SW62")
      (value "CHERRY_MX")
      (footprint "eagle-import:CHERRY_MX")
      (libsource (lib "eagle-import") (part "CHERRY_MX"))
    )
    (comp (ref "SW63")
      (value "CHERRY_MX")
      (footprint "eagle-import:CHERRY_MX")
      (libsource (lib "eagle-import") (part "CHERRY_MX"))
    )
    (comp (ref "SW64")
      (value "CHERRY_MX")
      (footprint "eagle-import:CHERRY_MX")
      (libsource (lib "eagle-import") (part "CHERRY_MX"))
    )
    (comp (ref "SW65")
      (value "CHERRY_MX")
      (footprint "eagle-import:CHERRY_MX")
      (libsource (lib "eagle-import") (part "CHERRY_MX"))
    )
    (comp (ref "SW66")
      (value "CHERRY_MX")
      (footprint "eagle-import:CHERRY_MX")
      (libsource (lib "eagle-import") (part "CHERRY_MX"))
    )
    (comp (ref "SW67")
      (value "CHERRY_MX")
      (footprint "eagle-import:CHERRY_MX")
      (libsource (lib "eagle-import") (part "CHERRY_MX"))
    )
    (comp (ref "SW68")
      (value "CHERRY_MX")
      (footprint "eagle-import:CHERRY_MX")
      (libsource (lib "eagle-import") (part "CHERRY_MX"))
    )
    (comp (ref "SW69")
      (value "CHERRY_MX")
      (footprint "eagle-import:CHERRY_MX")
      (libsource (lib "eagle-import") (part "CHERRY_MX"))
    )
    (comp (ref "SW70")
      (value "CHERRY_MX")
      (footprint "eagle-import:CHERRY_MX")
      (libsource (lib "eagle-import") (part "CHERRY_MX"))
    )
    (comp (ref "SW71")
      (value "CHERRY_MX")
      (footprint "eagle-import:CHERRY_MX")
      (libsource (lib "eagle-import") (part "CHERRY_MX"))
    )
    (comp (ref "SW72")
      (value "CHERRY_MX")
      (footprint "eagle-import:CHERRY_MX")
      (libsource (lib "eagle-import") (part "CHERRY_MX"))
    )
    (comp (ref "SW73")
      (value "CHERRY_MX")
      (footprint "eagle-import:CHERRY_MX")
      (libsource (lib "eagle-import") (part "CHERRY_MX"))
    )
    (comp (ref "SW74")
      (value "CHERRY_MX")
      (footprint "eagle-import:CHERRY_MX")
      (libsource (lib "eagle-import") (part "CHERRY_MX"))
    )
    (comp (ref "SW75")
      (value "CHERRY_MX")
      (footprint "eagle-import:CHERRY_MX")
      (libsource (lib "eagle-import") (part "CHERRY_MX"))
    )
    (comp (ref "SW76")
      (value "CHERRY_MX")
      (footprint "eagle-import:CHERRY_MX")
      (libsource (lib "eagle-import") (part "CHERRY_MX"))
    )
    (comp (ref "SW77")
      (value "CHERRY_MX")
      (footprint "eagle-import:CHERRY_MX")
      (libsource (lib "eagle-import") (part "CHERRY_MX"))
    )
    (comp (ref "SW78")
      (value "CHERRY_MX")
      (footprint "eagle-import:CHERRY_MX")
      (libsource (lib "eagle-import") (part "CHERRY_MX"))
    )
    (comp (ref "SW79")
      (value "CHERRY_MX")
      (footprint "eagle-import:CHERRY_MX")
      (libsource (lib "eagle-import") (part "CHERRY_MX"))
    )
    (comp (ref "SW80")
      (value "CHERRY_MX")
      (footprint "eagle-import:CHERRY_MX")
      (libsource (lib "eagle-import") (part "CHERRY_MX"))
    )
    (comp (ref "SW81")
      (value "CHERRY_MX")
      (footprint "eagle-import:CHERRY_MX")
      (libsource (lib "eagle-import") (part "CHERRY_MX"))
    )
    (comp (ref "SW82")
      (value "CHERRY_MX")
      (footprint "eagle-import:CHERRY_MX")
      (libsource (lib "eagle-import") (part "CHERRY_MX"))
    )
    (comp (ref "SW83")
      (value "CHERRY_MX")
      (footprint "eagle-import:CHERRY_MX")
      (libsource (lib "eagle-import") (part "CHERRY_MX"))
    )
    (comp (ref "SW84")
      (value "CHERRY_MX")
      (footprint "eagle-import:CHERRY_MX")
      (libsource (lib "eagle-import") (part "CHERRY_MX"))
    )
    (comp (ref "SW86")
      (value "CHERRY_MX")
      (footprint "eagle-import:CHERRY_MX")
      (libsource (lib "eagle-import") (part "CHERRY_MX"))
    )
    (comp (ref "SW87")
      (value "CHERRY_MX")
      (footprint "eagle-import:CHERRY_MX")
      (libsource (lib "eagle-import") (part "CHERRY_MX"))
    )
    (comp (ref "SW88")
      (value "CHERRY_MX")
      (footprint "eagle-import:CHERRY_MX")
      (libsource (lib "eagle-import") (part "CHERRY_MX"))
    )
    (comp (ref "SW89")
      (value "CHERRY_MX")
      (footprint "eagle-import:CHERRY_MX")
      (libsource (lib "eagle-import") (part "CHERRY_MX"))
    )
    (comp (ref "SW90")
      (value "CHERRY_MX")
      (footprint "eagle-import:CHERRY_MX")
      (libsource (lib "eagle-import") (part "CHERRY_MX"))
    )
    (comp (ref "SW91")
      (value "CHERRY_MX")
      (footprint "eagle-import:CHERRY_MX")
      (libsource (lib "eagle-import") (part "CHERRY_MX"))
    )
    (comp (ref "SW92")
      (value "CHERRY_MX")
      (footprint "eagle-import:CHERRY_MX")
      (libsource (lib "eagle-import") (part "CHERRY_MX"))
    )
  )
  (nets
    (net (code "1") (name "C1") (class "Default")
      (node (ref "SW1") (pin "1") (pinfunction "1_1") (pintype "bidirectional"))
      (node (ref "SW18") (pin "1") (pinfunction "1_1") (pintype "bidirectional"))
      (node (ref "SW36") (pin "1") (pinfunction "1_1") (pintype "bidirectional"))
      (node (ref "SW54") (pin "1") (pinfunction "1_1") (pintype "bidirectional"))
      (node (ref "SW68") (pin "1") (pinfunction "1_1") (pintype "bidirectional"))
      (node (ref "SW82") (pin "1") (pinfunction "1_1") (pintype "bidirectional"))
      (node (ref "U1") (pin "57") (pinfunction "PE8_57") (pintype "bidirectional"))
    )
    (net (code "2") (name "C2") (class "Default")
      (node (ref "SW19") (pin "1") (pinfunction "1_1") (pintype "bidirectional"))
      (node (ref "SW2") (pin "1") (pinfunction "1_1") (pintype "bidirectional"))
      (node (ref "SW37") (pin "1") (pinfunction "1_1") (pintype "bidirectional"))
      (node (ref "SW55") (pin "1") (pinfunction "1_1") (pintype "bidirectional"))
      (node (ref "SW69") (pin "1") (pinfunction "1_1") (pintype "bidirectional"))
      (node (ref "SW83") (pin "1") (pinfunction "1_1") (pintype "bidirectional"))
      (node (ref "U1") (pin "58") (pinfunction "PE9_58") (pintype "bidirectional"))
    )
    (net (code "3") (name "C3") (class "Default")
      (node (ref "SW20") (pin "1") (pinfunction "1_1") (pintype "bidirectional"))
      (node (ref "SW3") (pin "1") (pinfunction "1_1") (pintype "bidirectional"))
      (node (ref "SW38") (pin "1") (pinfunction "1_1") (pintype "bidirectional"))
      (node (ref "SW56") (pin "1") (pinfunction "1_1") (pintype "bidirectional"))
      (node (ref "SW70") (pin "1") (pinfunction "1_1") (pintype "bidirectional"))
      (node (ref "SW84") (pin "1") (pinfunction "1_1") (pintype "bidirectional"))
      (node (ref "U1") (pin "59") (pinfunction "PE10_59") (pintype "bidirectional"))
    )
    (net (code "4") (name "C4") (class "Default")
      (node (ref "SPACE") (pin "1") (pinfunction "1_1") (pintype "bidirectional"))
      (node (ref "SW21") (pin "1") (pinfunction "1_1") (pintype "bidirectional"))
      (node (ref "SW39") (pin "1") (pinfunction "1_1") (pintype "bidirectional"))
      (node (ref "SW4") (pin "1") (pinfunction "1_1") (pintype "bidirectional"))
      (node (ref "SW57") (pin "1") (pinfunction "1_1") (pintype "bidirectional"))
      (node (ref "SW71") (pin "1") (pinfunction "1_1") (pintype "bidirectional"))
      (node (ref "U1") (pin "60") (pinfunction "PE11_60") (pintype "bidirectional"))
    )
    (net (code "5") (name "C5") (class "Default")
      (node (ref "SW22") (pin "1") (pinfunction "1_1") (pintype "bidirectional"))
      (node (ref "SW40") (pin "1") (pinfunction "1_1") (pintype "bidirectional"))
      (node (ref "SW5") (pin "1") (pinfunction "1_1") (pintype "bidirectional"))
      (node (ref "SW58") (pin "1") (pinfunction "1_1") (pintype "bidirectional"))
      (node (ref "SW72") (pin "1") (pinfunction "1_1") (pintype "bidirectional"))
      (node (ref "SW86") (pin "1") (pinfunction "1_1") (pintype "bidirectional"))
      (node (ref "U1") (pin "61") (pinfunction "PE12_61") (pintype "bidirectional"))
    )
    (net (code "6") (name "C6") (class "Default")
      (node (ref "SW23") (pin "1") (pinfunction "1_1") (pintype "bidirectional"))
      (node (ref "SW41") (pin "1") (pinfunction "1_1") (pintype "bidirectional"))
      (node (ref "SW59") (pin "1") (pinfunction "1_1") (pintype "bidirectional"))
      (node (ref "SW6") (pin "1") (pinfunction "1_1") (pintype "bidirectional"))
      (node (ref "SW73") (pin "1") (pinfunction "1_1") (pintype "bidirectional"))
      (node (ref "SW87") (pin "1") (pinfunction "1_1") (pintype "bidirectional"))
      (node (ref "U1") (pin "62") (pinfunction "PE13_62") (pintype "bidirectional"))
    )
    (net (code "7") (name "C7") (class "Default")
      (node (ref "SW24") (pin "1") (pinfunction "1_1") (pintype "bidirectional"))
      (node (ref "SW42") (pin "1") (pinfunction "1_1") (pintype "bidirectional"))
      (node (ref "SW60") (pin "1") (pinfunction "1_1") (pintype "bidirectional"))
      (node (ref "SW7") (pin "1") (pinfunction "1_1") (pintype "bidirectional"))
      (node (ref "SW74") (pin "1") (pinfunction "1_1") (pintype "bidirectional"))
      (node (ref "SW88") (pin "1") (pinfunction "1_1") (pintype "bidirectional"))
      (node (ref "U1") (pin "63") (pinfunction "PE14_63") (pintype "bidirectional"))
    )
    (net (code "8") (name "C8") (class "Default")
      (node (ref "SW25") (pin "1") (pinfunction "1_1") (pintype "bidirectional"))
      (node (ref "SW43") (pin "1") (pinfunction "1_1") (pintype "bidirectional"))
      (node (ref "SW61") (pin "1") (pinfunction "1_1") (pintype "bidirectional"))
      (node (ref "SW75") (pin "1") (pinfunction "1_1") (pintype "bidirectional"))
      (node (ref "SW8") (pin "1") (pinfunction "1_1") (pintype "bidirectional"))
      (node (ref "SW89") (pin "1") (pinfunction "1_1") (pintype "bidirectional"))
      (node (ref "U1") (pin "64") (pinfunction "PE15_64") (pintype "bidirectional"))
    )
    (net (code "9") (name "C9") (class "Default")
      (node (ref "SW26") (pin "1") (pinfunction "1_1") (pintype "bidirectional"))
      (node (ref "SW44") (pin "1") (pinfunction "1_1") (pintype "bidirectional"))
      (node (ref "SW62") (pin "1") (pinfunction "1_1") (pintype "bidirectional"))
      (node (ref "SW76") (pin "1") (pinfunction "1_1") (pintype "bidirectional"))
      (node (ref "SW9") (pin "1") (pinfunction "1_1") (pintype "bidirectional"))
      (node (ref "SW90") (pin "1") (pinfunction "1_1") (pintype "bidirectional"))
      (node (ref "U1") (pin "9") (pinfunction "PC0_9") (pintype "bidirectional"))
    )
    (net (code "10") (name "C10") (class "Default")
      (node (ref "SW10") (pin "1") (pinfunction "1_1") (pintype "bidirectional"))
      (node (ref "SW27") (pin "1") (pinfunction "1_1") (pintype "bidirectional"))
      (node (ref "SW45") (pin "1") (pinfunction "1_1") (pintype "bidirectional"))
      (node (ref "SW63") (pin "1") (pinfunction "1_1") (pintype "bidirectional"))
      (node (ref "SW77") (pin "1") (pinfunction "1_1") (pintype "bidirectional"))
      (node (ref "SW91") (pin "1") (pinfunction "1_1") (pintype "bidirectional"))
      (node (ref "U1") (pin "10") (pinfunction "PC1_10") (pintype "bidirectional"))
    )
    (net (code "11") (name "C11") (class "Default")
      (node (ref "SW11") (pin "1") (pinfunction "1_1") (pintype "bidirectional"))
      (node (ref "SW28") (pin "1") (pinfunction "1_1") (pintype "bidirectional"))
      (node (ref "SW46") (pin "1") (pinfunction "1_1") (pintype "bidirectional"))
      (node (ref "SW64") (pin "1") (pinfunction "1_1") (pintype "bidirectional"))
      (node (ref "SW78") (pin "1") (pinfunction "1_1") (pintype "bidirectional"))
      (node (ref "SW92") (pin "1") (pinfunction "1_1") (pintype "bidirectional"))
      (node (ref "U1") (pin "11") (pinfunction "PC2_11") (pintype "bidirectional"))
    )
    (net (code "12") (name "C12") (class "Default")
      (node (ref "SW12") (pin "1") (pinfunction "1_1") (pintype "bidirectional"))
      (node (ref "SW29") (pin "1") (pinfunction "1_1") (pintype "bidirectional"))
      (node (ref "SW47") (pin "1") (pinfunction "1_1") (pintype "bidirectional"))
      (node (ref "SW65") (pin "1") (pinfunction "1_1") (pintype "bidirectional"))
      (node (ref "SW79") (pin "1") (pinfunction "1_1") (pintype "bidirectional"))
      (node (ref "U1") (pin "12") (pinfunction "PC3_12") (pintype "bidirectional"))
    )
    (net (code "13") (name "C13") (class "Default")
      (node (ref "SW13") (pin "1") (pinfunction "1_1") (pintype "bidirectional"))
      (node (ref "SW30") (pin "1") (pinfunction "1_1") (pintype "bidirectional"))
      (node (ref "SW48") (pin "1") (pinfunction "1_1") (pintype "bidirectional"))
      (node (ref "SW66") (pin "1") (pinfunction "1_1") (pintype "bidirectional"))
      (node (ref "SW80") (pin "1") (pinfunction "1_1") (pintype "bidirectional"))
      (node (ref "U1") (pin "13") (pinfunction "PC4_13") (pintype "bidirectional"))
    )
    (net (code "14") (name "C14") (class "Default")
      (node (ref "SW14") (pin "1") (pinfunction "1_1") (pintype "bidirectional"))
      (node (ref "SW31") (pin "1") (pinfunction "1_1") (pintype "bidirectional"))
      (node (ref "SW49") (pin "1") (pinfunction "1_1") (pintype "bidirectional"))
      (node (ref "SW67") (pin "1") (pinfunction "1_1") (pintype "bidirectional"))
      (node (ref "SW81") (pin "1") (pinfunction "1_1") (pintype "bidirectional"))
      (node (ref "U1") (pin "14") (pinfunction "PC5_14") (pintype "bidirectional"))
    )
    (net (code "15") (name "C15") (class "Default")
      (node (ref "SW15") (pin "1") (pinfunction "1_1") (pintype "bidirectional"))
      (node (ref "SW32") (pin "1") (pinfunction "1_1") (pintype "bidirectional"))
      (node (ref "SW50") (pin "1") (pinfunction "1_1") (pintype "bidirectional"))
      (node (ref "U1") (pin "15") (pinfunction "PB7_15") (pintype "bidirectional"))
    )
    (net (code "16") (name "C16") (class "Default")
      (node (ref "SW16") (pin "1") (pinfunction "1_1") (pintype "bidirectional"))
      (node (ref "SW33") (pin "1") (pinfunction "1_1") (pintype "bidirectional"))
      (node (ref "SW51") (pin "1") (pinfunction "1_1") (pintype "bidirectional"))
      (node (ref "U1") (pin "16") (pinfunction "PB8_16") (pintype "bidirectional"))
    )
    (net (code "17") (name "C17") (class "Default")
      (node (ref "SW17") (pin "1") (pinfunction "1_1") (pintype "bidirectional"))
      (node (ref "SW34") (pin "1") (pinfunction "1_1") (pintype "bidirectional"))
      (node (ref "SW52") (pin "1") (pinfunction "1_1") (pintype "bidirectional"))
      (node (ref "U1") (pin "17") (pinfunction "PA8_17") (pintype "bidirectional"))
    )
    (net (code "18") (name "C18") (class "Default")
      (node (ref "SW35") (pin "1") (pinfunction "1_1") (pintype "bidirectional"))
      (node (ref "SW53") (pin "1") (pinfunction "1_1") (pintype "bidirectional"))
      (node (ref "U1") (pin "18") (pinfunction "PA9_18") (pintype "bidirectional"))
    )
    (net (code "19") (name "GND") (class "Default")
      (node (ref "ARM_20_HEADER") (pin "10") (pinfunction "10_10") (pintype "passive"))
      (node (ref "ARM_20_HEADER") (pin "12") (pinfunction "12_12") (pintype "passive"))
      (node (ref "ARM_20_HEADER") (pin "14") (pinfunction "14_14") (pintype "passive"))
      (node (ref "ARM_20_HEADER") (pin "16") (pinfunction "16_16") (pintype "passive"))
      (node (ref "ARM_20_HEADER") (pin "18") (pinfunction "18_18") (pintype "passive"))
      (node (ref "ARM_20_HEADER") (pin "20") (pinfunction "20_20") (pintype "passive"))
      (node (ref "ARM_20_HEADER") (pin "4") (pinfunction "4_4") (pintype "passive"))
      (node (ref "ARM_20_HEADER") (pin "6") (pinfunction "6_6") (pintype "passive"))
      (node (ref "ARM_20_HEADER") (pin "8") (pinfunction "8_8") (pintype "passive"))
      (node (ref "C1") (pin "2") (pinfunction "2_2") (pintype "passive"))
      (node (ref "C10") (pin "2") (pinfunction "2_2") (pintype "passive"))
      (node (ref "C11") (pin "2") (pinfunction "2_2") (pintype "passive"))
      (node (ref "C12") (pin "2") (pinfunction "2_2") (pintype "passive"))
      (node (ref "C13") (pin "2") (pinfunction "2_2") (pintype "passive"))
      (node (ref "C14") (pin "2") (pinfunction "2_2") (pintype "passive"))
      (node (ref "C15") (pin "2") (pinfunction "2_2") (pintype "passive"))
      (node (ref "C16") (pin "2") (pinfunction "2_2") (pintype "passive"))
      (node (ref "C17") (pin "2") (pinfunction "2_2") (pintype "passive"))
      (node (ref "C18") (pin "2") (pinfunction "2_2") (pintype "passive"))
      (node (ref "C2") (pin "2") (pinfunction "2_2") (pintype "passive"))
      (node (ref "C3") (pin "2") (pinfunction "2_2") (pintype "passive"))
      (node (ref "C4") (pin "2") (pinfunction "2_2") (pintype "passive"))
      (node (ref "C5") (pin "2") (pinfunction "2_2") (pintype "passive"))
      (node (ref "C6") (pin "2") (pinfunction "2_2") (pintype "passive"))
      (node (ref "C7") (pin "2") (pinfunction "2_2") (pintype "passive"))
      (node (ref "C8") (pin "2") (pinfunction "2_2") (pintype "passive"))
      (node (ref "C9") (pin "2") (pinfunction "2_2") (pintype "passive"))
      (node (ref "J1") (pin "GND") (pinfunction "GND_GND") (pintype "bidirectional"))
      (node (ref "SILABS_DEBUG") (pin "3") (pinfunction "3_3") (pintype "passive"))
      (node (ref "SILABS_DEBUG") (pin "5") (pinfunction "5_5") (pintype "passive"))
      (node (ref "SILABS_DEBUG") (pin "9") (pinfunction "9_9") (pintype "passive"))
      (node (ref "U1") (pin "22") (pinfunction "VSS_22") (pintype "bidirectional"))
      (node (ref "U1") (pin "56") (pinfunction "VSS_56") (pintype "bidirectional"))
      (node (ref "U1") (pin "8") (pinfunction "VSS_8") (pintype "bidirectional"))
      (node (ref "U2") (pin "3") (pinfunction "GND_3") (pintype "bidirectional"))
    )
    (net (code "20") (name "Net-(CAPS-PadA)") (class "Default")
      (node (ref "CAPS") (pin "A") (pinfunction "A_A") (pintype "passive"))
      (node (ref "R3") (pin "2") (pinfunction "2_2") (pintype "passive"))
    )
    (net (code "21") (name "Net-(D1-Pad2)") (class "Default")
      (node (ref "D1") (pin "2") (pinfunction "2_2") (pintype "bidirectional"))
      (node (ref "SW1") (pin "2") (pinfunction "2_2") (pintype "bidirectional"))
    )
    (net (code "22") (name "Net-(D2-Pad2)") (class "Default")
      (node (ref "D2") (pin "2") (pinfunction "2_2") (pintype "bidirectional"))
      (node (ref "SW18") (pin "2") (pinfunction "2_2") (pintype "bidirectional"))
    )
    (net (code "23") (name "Net-(D3-Pad2)") (class "Default")
      (node (ref "D3") (pin "2") (pinfunction "2_2") (pintype "bidirectional"))
      (node (ref "SW36") (pin "2") (pinfunction "2_2") (pintype "bidirectional"))
    )
    (net (code "24") (name "Net-(D4-Pad2)") (class "Default")
      (node (ref "D4") (pin "2") (pinfunction "2_2") (pintype "bidirectional"))
      (node (ref "SW54") (pin "2") (pinfunction "2_2") (pintype "bidirectional"))
    )
    (net (code "25") (name "Net-(D5-Pad2)") (class "Default")
      (node (ref "D5") (pin "2") (pinfunction "2_2") (pintype "bidirectional"))
      (node (ref "SW68") (pin "2") (pinfunction "2_2") (pintype "bidirectional"))
    )
    (net (code "26") (name "Net-(D6-Pad2)") (class "Default")
      (node (ref "D6") (pin "2") (pinfunction "2_2") (pintype "bidirectional"))
      (node (ref "SW82") (pin "2") (pinfunction "2_2") (pintype "bidirectional"))
    )
    (net (code "27") (name "Net-(D7-Pad2)") (class "Default")
      (node (ref "D7") (pin "2") (pinfunction "2_2") (pintype "bidirectional"))
      (node (ref "SW2") (pin "2") (pinfunction "2_2") (pintype "bidirectional"))
    )
    (net (code "28") (name "Net-(D8-Pad2)") (class "Default")
      (node (ref "D8") (pin "2") (pinfunction "2_2") (pintype "bidirectional"))
      (node (ref "SW19") (pin "2") (pinfunction "2_2") (pintype "bidirectional"))
    )
    (net (code "29") (name "Net-(D9-Pad2)") (class "Default")
      (node (ref "D9") (pin "2") (pinfunction "2_2") (pintype "bidirectional"))
      (node (ref "SW37") (pin "2") (pinfunction "2_2") (pintype "bidirectional"))
    )
    (net (code "30") (name "Net-(D10-Pad2)") (class "Default")
      (node (ref "D10") (pin "2") (pinfunction "2_2") (pintype "bidirectional"))
      (node (ref "SW55") (pin "2") (pinfunction "2_2") (pintype "bidirectional"))
    )
    (net (code "31") (name "Net-(D11-Pad2)") (class "Default")
      (node (ref "D11") (pin "2") (pinfunction "2_2") (pintype "bidirectional"))
      (node (ref "SW69") (pin "2") (pinfunction "2_2") (pintype "bidirectional"))
    )
    (net (code "32") (name "Net-(D12-Pad2)") (class "Default")
      (node (ref "D12") (pin "2") (pinfunction "2_2") (pintype "bidirectional"))
      (node (ref "SW83") (pin "2") (pinfunction "2_2") (pintype "bidirectional"))
    )
    (net (code "33") (name "Net-(D13-Pad2)") (class "Default")
      (node (ref "D13") (pin "2") (pinfunction "2_2") (pintype "bidirectional"))
      (node (ref "SW3") (pin "2") (pinfunction "2_2") (pintype "bidirectional"))
    )
    (net (code "34") (name "Net-(D14-Pad2)") (class "Default")
      (node (ref "D14") (pin "2") (pinfunction "2_2") (pintype "bidirectional"))
      (node (ref "SW20") (pin "2") (pinfunction "2_2") (pintype "bidirectional"))
    )
    (net (code "35") (name "Net-(D15-Pad2)") (class "Default")
      (node (ref "D15") (pin "2") (pinfunction "2_2") (pintype "bidirectional"))
      (node (ref "SW38") (pin "2") (pinfunction "2_2") (pintype "bidirectional"))
    )
    (net (code "36") (name "Net-(D16-Pad2)") (class "Default")
      (node (ref "D16") (pin "2") (pinfunction "2_2") (pintype "bidirectional"))
      (node (ref "SW56") (pin "2") (pinfunction "2_2") (pintype "bidirectional"))
    )
    (net (code "37") (name "Net-(D17-Pad2)") (class "Default")
      (node (ref "D17") (pin "2") (pinfunction "2_2") (pintype "bidirectional"))
      (node (ref "SW70") (pin "2") (pinfunction "2_2") (pintype "bidirectional"))
    )
    (net (code "38") (name "Net-(D18-Pad2)") (class "Default")
      (node (ref "D18") (pin "2") (pinfunction "2_2") (pintype "bidirectional"))
      (node (ref "SW84") (pin "2") (pinfunction "2_2") (pintype "bidirectional"))
    )
    (net (code "39") (name "Net-(D19-Pad2)") (class "Default")
      (node (ref "D19") (pin "2") (pinfunction "2_2") (pintype "bidirectional"))
      (node (ref "SW4") (pin "2") (pinfunction "2_2") (pintype "bidirectional"))
    )
    (net (code "40") (name "Net-(D20-Pad2)") (class "Default")
      (node (ref "D20") (pin "2") (pinfunction "2_2") (pintype "bidirectional"))
      (node (ref "SW21") (pin "2") (pinfunction "2_2") (pintype "bidirectional"))
    )
    (net (code "41") (name "Net-(D21-Pad2)") (class "Default")
      (node (ref "D21") (pin "2") (pinfunction "2_2") (pintype "bidirectional"))
      (node (ref "SW39") (pin "2") (pinfunction "2_2") (pintype "bidirectional"))
    )
    (net (code "42") (name "Net-(D22-Pad2)") (class "Default")
      (node (ref "D22") (pin "2") (pinfunction "2_2") (pintype "bidirectional"))
      (node (ref "SW57") (pin "2") (pinfunction "2_2") (pintype "bidirectional"))
    )
    (net (code "43") (name "Net-(D23-Pad2)") (class "Default")
      (node (ref "D23") (pin "2") (pinfunction "2_2") (pintype "bidirectional"))
      (node (ref "SW71") (pin "2") (pinfunction "2_2") (pintype "bidirectional"))
    )
    (net (code "44") (name "Net-(D24-Pad2)") (class "Default")
      (node (ref "D24") (pin "2") (pinfunction "2_2") (pintype "bidirectional"))
      (node (ref "SPACE") (pin "2") (pinfunction "2_2") (pintype "bidirectional"))
    )
    (net (code "45") (name "Net-(D25-Pad2)") (class "Default")
      (node (ref "D25") (pin "2") (pinfunction "2_2") (pintype "bidirectional"))
      (node (ref "SW5") (pin "2") (pinfunction "2_2") (pintype "bidirectional"))
    )
    (net (code "46") (name "Net-(D26-Pad2)") (class "Default")
      (node (ref "D26") (pin "2") (pinfunction "2_2") (pintype "bidirectional"))
      (node (ref "SW22") (pin "2") (pinfunction "2_2") (pintype "bidirectional"))
    )
    (net (code "47") (name "Net-(D27-Pad2)") (class "Default")
      (node (ref "D27") (pin "2") (pinfunction "2_2") (pintype "bidirectional"))
      (node (ref "SW40") (pin "2") (pinfunction "2_2") (pintype "bidirectional"))
    )
    (net (code "48") (name "Net-(D28-Pad2)") (class "Default")
      (node (ref "D28") (pin "2") (pinfunction "2_2") (pintype "bidirectional"))
      (node (ref "SW58") (pin "2") (pinfunction "2_2") (pintype "bidirectional"))
    )
    (net (code "49") (name "Net-(D29-Pad2)") (class "Default")
      (node (ref "D29") (pin "2") (pinfunction "2_2") (pintype "bidirectional"))
      (node (ref "SW72") (pin "2") (pinfunction "2_2") (pintype "bidirectional"))
    )
    (net (code "50") (name "Net-(D30-Pad2)") (class "Default")
      (node (ref "D30") (pin "2") (pinfunction "2_2") (pintype "bidirectional"))
      (node (ref "SW86") (pin "2") (pinfunction "2_2") (pintype "bidirectional"))
    )
    (net (code "51") (name "Net-(D31-Pad2)") (class "Default")
      (node (ref "D31") (pin "2") (pinfunction "2_2") (pintype "bidirectional"))
      (node (ref "SW6") (pin "2") (pinfunction "2_2") (pintype "bidirectional"))
    )
    (net (code "52") (name "Net-(D32-Pad2)") (class "Default")
      (node (ref "D32") (pin "2") (pinfunction "2_2") (pintype "bidirectional"))
      (node (ref "SW23") (pin "2") (pinfunction "2_2") (pintype "bidirectional"))
    )
    (net (code "53") (name "Net-(D33-Pad2)") (class "Default")
      (node (ref "D33") (pin "2") (pinfunction "2_2") (pintype "bidirectional"))
      (node (ref "SW41") (pin "2") (pinfunction "2_2") (pintype "bidirectional"))
    )
    (net (code "54") (name "Net-(D34-Pad2)") (class "Default")
      (node (ref "D34") (pin "2") (pinfunction "2_2") (pintype "bidirectional"))
      (node (ref "SW59") (pin "2") (pinfunction "2_2") (pintype "bidirectional"))
    )
    (net (code "55") (name "Net-(D35-Pad2)") (class "Default")
      (node (ref "D35") (pin "2") (pinfunction "2_2") (pintype "bidirectional"))
      (node (ref "SW73") (pin "2") (pinfunction "2_2") (pintype "bidirectional"))
    )
    (net (code "56") (name "Net-(D36-Pad2)") (class "Default")
      (node (ref "D36") (pin "2") (pinfunction "2_2") (pintype "bidirectional"))
      (node (ref "SW87") (pin "2") (pinfunction "2_2") (pintype "bidirectional"))
    )
    (net (code "57") (name "Net-(D37-Pad2)") (class "Default")
      (node (ref "D37") (pin "2") (pinfunction "2_2") (pintype "bidirectional"))
      (node (ref "SW7") (pin "2") (pinfunction "2_2") (pintype "bidirectional"))
    )
    (net (code "58") (name "Net-(D38-Pad2)") (class "Default")
      (node (ref "D38") (pin "2") (pinfunction "2_2") (pintype "bidirectional"))
      (node (ref "SW24") (pin "2") (pinfunction "2_2") (pintype "bidirectional"))
    )
    (net (code "59") (name "Net-(D39-Pad2)") (class "Default")
      (node (ref "D39") (pin "2") (pinfunction "2_2") (pintype "bidirectional"))
      (node (ref "SW42") (pin "2") (pinfunction "2_2") (pintype "bidirectional"))
    )
    (net (code "60") (name "Net-(D40-Pad2)") (class "Default")
      (node (ref "D40") (pin "2") (pinfunction "2_2") (pintype "bidirectional"))
      (node (ref "SW60") (pin "2") (pinfunction "2_2") (pintype "bidirectional"))
    )
    (net (code "61") (name "Net-(D41-Pad2)") (class "Default")
      (node (ref "D41") (pin "2") (pinfunction "2_2") (pintype "bidirectional"))
      (node (ref "SW74") (pin "2") (pinfunction "2_2") (pintype "bidirectional"))
    )
    (net (code "62") (name "Net-(D42-Pad2)") (class "Default")
      (node (ref "D42") (pin "2") (pinfunction "2_2") (pintype "bidirectional"))
      (node (ref "SW88") (pin "2") (pinfunction "2_2") (pintype "bidirectional"))
    )
    (net (code "63") (name "Net-(D43-Pad2)") (class "Default")
      (node (ref "D43") (pin "2") (pinfunction "2_2") (pintype "bidirectional"))
      (node (ref "SW8") (pin "2") (pinfunction "2_2") (pintype "bidirectional"))
    )
    (net (code "64") (name "Net-(D44-Pad2)") (class "Default")
      (node (ref "D44") (pin "2") (pinfunction "2_2") (pintype "bidirectional"))
      (node (ref "SW25") (pin "2") (pinfunction "2_2") (pintype "bidirectional"))
    )
    (net (code "65") (name "Net-(D45-Pad2)") (class "Default")
      (node (ref "D45") (pin "2") (pinfunction "2_2") (pintype "bidirectional"))
      (node (ref "SW43") (pin "2") (pinfunction "2_2") (pintype "bidirectional"))
    )
    (net (code "66") (name "Net-(D46-Pad2)") (class "Default")
      (node (ref "D46") (pin "2") (pinfunction "2_2") (pintype "bidirectional"))
      (node (ref "SW61") (pin "2") (pinfunction "2_2") (pintype "bidirectional"))
    )
    (net (code "67") (name "Net-(D47-Pad2)") (class "Default")
      (node (ref "D47") (pin "2") (pinfunction "2_2") (pintype "bidirectional"))
      (node (ref "SW75") (pin "2") (pinfunction "2_2") (pintype "bidirectional"))
    )
    (net (code "68") (name "Net-(D48-Pad2)") (class "Default")
      (node (ref "D48") (pin "2") (pinfunction "2_2") (pintype "bidirectional"))
      (node (ref "SW89") (pin "2") (pinfunction "2_2") (pintype "bidirectional"))
    )
    (net (code "69") (name "Net-(D49-Pad2)") (class "Default")
      (node (ref "D49") (pin "2") (pinfunction "2_2") (pintype "bidirectional"))
      (node (ref "SW9") (pin "2") (pinfunction "2_2") (pintype "bidirectional"))
    )
    (net (code "70") (name "Net-(D50-Pad2)") (class "Default")
      (node (ref "D50") (pin "2") (pinfunction "2_2") (pintype "bidirectional"))
      (node (ref "SW26") (pin "2") (pinfunction "2_2") (pintype "bidirectional"))
    )
    (net (code "71") (name "Net-(D51-Pad2)") (class "Default")
      (node (ref "D51") (pin "2") (pinfunction "2_2") (pintype "bidirectional"))
      (node (ref "SW44") (pin "2") (pinfunction "2_2") (pintype "bidirectional"))
    )
    (net (code "72") (name "Net-(D52-Pad2)") (class "Default")
      (node (ref "D52") (pin "2") (pinfunction "2_2") (pintype "bidirectional"))
      (node (ref "SW62") (pin "2") (pinfunction "2_2") (pintype "bidirectional"))
    )
    (net (code "73") (name "Net-(D53-Pad2)") (class "Default")
      (node (ref "D53") (pin "2") (pinfunction "2_2") (pintype "bidirectional"))
      (node (ref "SW76") (pin "2") (pinfunction "2_2") (pintype "bidirectional"))
    )
    (net (code "74") (name "Net-(D54-Pad2)") (class "Default")
      (node (ref "D54") (pin "2") (pinfunction "2_2") (pintype "bidirectional"))
      (node (ref "SW90") (pin "2") (pinfunction "2_2") (pintype "bidirectional"))
    )
    (net (code "75") (name "Net-(D55-Pad2)") (class "Default")
      (node (ref "D55") (pin "2") (pinfunction "2_2") (pintype "bidirectional"))
      (node (ref "SW10") (pin "2") (pinfunction "2_2") (pintype "bidirectional"))
    )
    (net (code "76") (name "Net-(D56-Pad2)") (class "Default")
      (node (ref "D56") (pin "2") (pinfunction "2_2") (pintype "bidirectional"))
      (node (ref "SW27") (pin "2") (pinfunction "2_2") (pintype "bidirectional"))
    )
    (net (code "77") (name "Net-(D57-Pad2)") (class "Default")
      (node (ref "D57") (pin "2") (pinfunction "2_2") (pintype "bidirectional"))
      (node (ref "SW45") (pin "2") (pinfunction "2_2") (pintype "bidirectional"))
    )
    (net (code "78") (name "Net-(D58-Pad2)") (class "Default")
      (node (ref "D58") (pin "2") (pinfunction "2_2") (pintype "bidirectional"))
      (node (ref "SW63") (pin "2") (pinfunction "2_2") (pintype "bidirectional"))
    )
    (net (code "79") (name "Net-(D59-Pad2)") (class "Default")
      (node (ref "D59") (pin "2") (pinfunction "2_2") (pintype "bidirectional"))
      (node (ref "SW77") (pin "2") (pinfunction "2_2") (pintype "bidirectional"))
    )
    (net (code "80") (name "Net-(D60-Pad2)") (class "Default")
      (node (ref "D60") (pin "2") (pinfunction "2_2") (pintype "bidirectional"))
      (node (ref "SW91") (pin "2") (pinfunction "2_2") (pintype "bidirectional"))
    )
    (net (code "81") (name "Net-(D61-Pad2)") (class "Default")
      (node (ref "D61") (pin "2") (pinfunction "2_2") (pintype "bidirectional"))
      (node (ref "SW11") (pin "2") (pinfunction "2_2") (pintype "bidirectional"))
    )
    (net (code "82") (name "Net-(D62-Pad2)") (class "Default")
      (node (ref "D62") (pin "2") (pinfunction "2_2") (pintype "bidirectional"))
      (node (ref "SW28") (pin "2") (pinfunction "2_2") (pintype "bidirectional"))
    )
    (net (code "83") (name "Net-(D63-Pad2)") (class "Default")
      (node (ref "D63") (pin "2") (pinfunction "2_2") (pintype "bidirectional"))
      (node (ref "SW46") (pin "2") (pinfunction "2_2") (pintype "bidirectional"))
    )
    (net (code "84") (name "Net-(D64-Pad2)") (class "Default")
      (node (ref "D64") (pin "2") (pinfunction "2_2") (pintype "bidirectional"))
      (node (ref "SW64") (pin "2") (pinfunction "2_2") (pintype "bidirectional"))
    )
    (net (code "85") (name "Net-(D65-Pad2)") (class "Default")
      (node (ref "D65") (pin "2") (pinfunction "2_2") (pintype "bidirectional"))
      (node (ref "SW78") (pin "2") (pinfunction "2_2") (pintype "bidirectional"))
    )
    (net (code "86") (name "Net-(D66-Pad2)") (class "Default")
      (node (ref "D66") (pin "2") (pinfunction "2_2") (pintype "bidirectional"))
      (node (ref "SW92") (pin "2") (pinfunction "2_2") (pintype "bidirectional"))
    )
    (net (code "87") (name "Net-(D67-Pad2)") (class "Default")
      (node (ref "D67") (pin "2") (pinfunction "2_2") (pintype "bidirectional"))
      (node (ref "SW12") (pin "2") (pinfunction "2_2") (pintype "bidirectional"))
    )
    (net (code "88") (name "Net-(D68-Pad2)") (class "Default")
      (node (ref "D68") (pin "2") (pinfunction "2_2") (pintype "bidirectional"))
      (node (ref "SW29") (pin "2") (pinfunction "2_2") (pintype "bidirectional"))
    )
    (net (code "89") (name "Net-(D69-Pad2)") (class "Default")
      (node (ref "D69") (pin "2") (pinfunction "2_2") (pintype "bidirectional"))
      (node (ref "SW47") (pin "2") (pinfunction "2_2") (pintype "bidirectional"))
    )
    (net (code "90") (name "Net-(D70-Pad2)") (class "Default")
      (node (ref "D70") (pin "2") (pinfunction "2_2") (pintype "bidirectional"))
      (node (ref "SW65") (pin "2") (pinfunction "2_2") (pintype "bidirectional"))
    )
    (net (code "91") (name "Net-(D71-Pad2)") (class "Default")
      (node (ref "D71") (pin "2") (pinfunction "2_2") (pintype "bidirectional"))
      (node (ref "SW79") (pin "2") (pinfunction "2_2") (pintype "bidirectional"))
    )
    (net (code "92") (name "Net-(D72-Pad2)") (class "Default")
      (node (ref "D72") (pin "2") (pinfunction "2_2") (pintype "bidirectional"))
      (node (ref "SW13") (pin "2") (pinfunction "2_2") (pintype "bidirectional"))
    )
    (net (code "93") (name "Net-(D73-Pad2)") (class "Default")
      (node (ref "D73") (pin "2") (pinfunction "2_2") (pintype "bidirectional"))
      (node (ref "SW30") (pin "2") (pinfunction "2_2") (pintype "bidirectional"))
    )
    (net (code "94") (name "Net-(D74-Pad2)") (class "Default")
      (node (ref "D74") (pin "2") (pinfunction "2_2") (pintype "bidirectional"))
      (node (ref "SW48") (pin "2") (pinfunction "2_2") (pintype "bidirectional"))
    )
    (net (code "95") (name "Net-(D75-Pad2)") (class "Default")
      (node (ref "D75") (pin "2") (pinfunction "2_2") (pintype "bidirectional"))
      (node (ref "SW66") (pin "2") (pinfunction "2_2") (pintype "bidirectional"))
    )
    (net (code "96") (name "Net-(D76-Pad2)") (class "Default")
      (node (ref "D76") (pin "2") (pinfunction "2_2") (pintype "bidirectional"))
      (node (ref "SW80") (pin "2") (pinfunction "2_2") (pintype "bidirectional"))
    )
    (net (code "97") (name "Net-(D77-Pad2)") (class "Default")
      (node (ref "D77") (pin "2") (pinfunction "2_2") (pintype "bidirectional"))
      (node (ref "SW14") (pin "2") (pinfunction "2_2") (pintype "bidirectional"))
    )
    (net (code "98") (name "Net-(D78-Pad2)") (class "Default")
      (node (ref "D78") (pin "2") (pinfunction "2_2") (pintype "bidirectional"))
      (node (ref "SW31") (pin "2") (pinfunction "2_2") (pintype "bidirectional"))
    )
    (net (code "99") (name "Net-(D79-Pad2)") (class "Default")
      (node (ref "D79") (pin "2") (pinfunction "2_2") (pintype "bidirectional"))
      (node (ref "SW49") (pin "2") (pinfunction "2_2") (pintype "bidirectional"))
    )
    (net (code "100") (name "Net-(D80-Pad2)") (class "Default")
      (node (ref "D80") (pin "2") (pinfunction "2_2") (pintype "bidirectional"))
      (node (ref "SW67") (pin "2") (pinfunction "2_2") (pintype "bidirectional"))
    )
    (net (code "101") (name "Net-(D81-Pad2)") (class "Default")
      (node (ref "D81") (pin "2") (pinfunction "2_2") (pintype "bidirectional"))
      (node (ref "SW81") (pin "2") (pinfunction "2_2") (pintype "bidirectional"))
    )
    (net (code "102") (name "Net-(D82-Pad2)") (class "Default")
      (node (ref "D82") (pin "2") (pinfunction "2_2") (pintype "bidirectional"))
      (node (ref "SW15") (pin "2") (pinfunction "2_2") (pintype "bidirectional"))
    )
    (net (code "103") (name "Net-(D83-Pad2)") (class "Default")
      (node (ref "D83") (pin "2") (pinfunction "2_2") (pintype "bidirectional"))
      (node (ref "SW32") (pin "2") (pinfunction "2_2") (pintype "bidirectional"))
    )
    (net (code "104") (name "Net-(D84-Pad2)") (class "Default")
      (node (ref "D84") (pin "2") (pinfunction "2_2") (pintype "bidirectional"))
      (node (ref "SW50") (pin "2") (pinfunction "2_2") (pintype "bidirectional"))
    )
    (net (code "105") (name "Net-(D85-Pad2)") (class "Default")
      (node (ref "D85") (pin "2") (pinfunction "2_2") (pintype "bidirectional"))
      (node (ref "SW16") (pin "2") (pinfunction "2_2") (pintype "bidirectional"))
    )
    (net (code "106") (name "Net-(D86-Pad2)") (class "Default")
      (node (ref "D86") (pin "2") (pinfunction "2_2") (pintype "bidirectional"))
      (node (ref "SW33") (pin "2") (pinfunction "2_2") (pintype "bidirectional"))
    )
    (net (code "107") (name "Net-(D87-Pad2)") (class "Default")
      (node (ref "D87") (pin "2") (pinfunction "2_2") (pintype "bidirectional"))
      (node (ref "SW51") (pin "2") (pinfunction "2_2") (pintype "bidirectional"))
    )
    (net (code "108") (name "Net-(D88-Pad2)") (class "Default")
      (node (ref "D88") (pin "2") (pinfunction "2_2") (pintype "bidirectional"))
      (node (ref "SW17") (pin "2") (pinfunction "2_2") (pintype "bidirectional"))
    )
    (net (code "109") (name "Net-(D89-Pad2)") (class "Default")
      (node (ref "D89") (pin "2") (pinfunction "2_2") (pintype "bidirectional"))
      (node (ref "SW34") (pin "2") (pinfunction "2_2") (pintype "bidirectional"))
    )
    (net (code "110") (name "Net-(D90-Pad2)") (class "Default")
      (node (ref "D90") (pin "2") (pinfunction "2_2") (pintype "bidirectional"))
      (node (ref "SW52") (pin "2") (pinfunction "2_2") (pintype "bidirectional"))
    )
    (net (code "111") (name "Net-(D91-Pad2)") (class "Default")
      (node (ref "D91") (pin "2") (pinfunction "2_2") (pintype "bidirectional"))
      (node (ref "SW35") (pin "2") (pinfunction "2_2") (pintype "bidirectional"))
    )
    (net (code "112") (name "Net-(D92-Pad2)") (class "Default")
      (node (ref "D92") (pin "2") (pinfunction "2_2") (pintype "bidirectional"))
      (node (ref "SW53") (pin "2") (pinfunction "2_2") (pintype "bidirectional"))
    )
    (net (code "113") (name "Net-(LED1\\-PadA)") (class "Default")
      (node (ref "LED1\\") (pin "A") (pinfunction "A_A") (pintype "passive"))
      (node (ref "R5") (pin "2") (pinfunction "2_2") (pintype "passive"))
    )
    (net (code "114") (name "Net-(Q1-2)") (class "Default")
      (node (ref "C15") (pin "1") (pinfunction "1_1") (pintype "passive"))
      (node (ref "Q1") (pin "3") (pinfunction "2_3") (pintype "passive"))
      (node (ref "U1") (pin "25") (pinfunction "PB14_25") (pintype "bidirectional"))
    )
    (net (code "115") (name "Net-(R4-Pad2)") (class "Default")
      (node (ref "R4") (pin "2") (pinfunction "2_2") (pintype "passive"))
      (node (ref "SCROLL") (pin "A") (pinfunction "A_A") (pintype "passive"))
    )
    (net (code "116") (name "Net-(SJ1-Pad1)") (class "Default")
      (node (ref "SJ1") (pin "1") (pinfunction "1_1") (pintype "passive"))
      (node (ref "TP1") (pin "TP") (pinfunction "TP_TP") (pintype "input"))
    )
    (net (code "117") (name "Net-(SJ2-Pad3)") (class "Default")
      (node (ref "SJ2") (pin "3") (pinfunction "3_3") (pintype "passive"))
      (node (ref "TP2") (pin "TP") (pinfunction "TP_TP") (pintype "input"))
    )
    (net (code "118") (name "Net-(U1-DECOUPLE)") (class "Default")
      (node (ref "C3") (pin "1") (pinfunction "1_1") (pintype "passive"))
      (node (ref "U1") (pin "40") (pinfunction "DECOUPLE_40") (pintype "bidirectional"))
    )
    (net (code "119") (name "Net-(U1-PA10)") (class "Default")
      (node (ref "TP16") (pin "TP") (pinfunction "TP_TP") (pintype "input"))
      (node (ref "U1") (pin "19") (pinfunction "PA10_19") (pintype "bidirectional"))
    )
    (net (code "120") (name "Net-(U1-PB11)") (class "Default")
      (node (ref "TP15") (pin "TP") (pinfunction "TP_TP") (pintype "input"))
      (node (ref "U1") (pin "21") (pinfunction "PB11_21") (pintype "bidirectional"))
    )
    (net (code "121") (name "Net-(U1-PB13)") (class "Default")
      (node (ref "C14") (pin "1") (pinfunction "1_1") (pintype "passive"))
      (node (ref "Q1") (pin "1") (pinfunction "1_1") (pintype "passive"))
      (node (ref "U1") (pin "24") (pinfunction "PB13_24") (pintype "bidirectional"))
    )
    (net (code "122") (name "Net-(U1-PC6)") (class "Default")
      (node (ref "TP8") (pin "TP") (pinfunction "TP_TP") (pintype "input"))
      (node (ref "U1") (pin "37") (pinfunction "PC6_37") (pintype "bidirectional"))
    )
    (net (code "123") (name "Net-(U1-PC7)") (class "Default")
      (node (ref "TP7") (pin "TP") (pinfunction "TP_TP") (pintype "input"))
      (node (ref "U1") (pin "38") (pinfunction "PC7_38") (pintype "bidirectional"))
    )
    (net (code "124") (name "Net-(U1-PC8)") (class "Default")
      (node (ref "TP5") (pin "TP") (pinfunction "TP_TP") (pintype "input"))
      (node (ref "U1") (pin "41") (pinfunction "PC8_41") (pintype "bidirectional"))
    )
    (net (code "125") (name "Net-(U1-PC9)") (class "Default")
      (node (ref "TP4") (pin "TP") (pinfunction "TP_TP") (pintype "input"))
      (node (ref "U1") (pin "42") (pinfunction "PC9_42") (pintype "bidirectional"))
    )
    (net (code "126") (name "Net-(U1-PC10)") (class "Default")
      (node (ref "TP3") (pin "TP") (pinfunction "TP_TP") (pintype "input"))
      (node (ref "U1") (pin "43") (pinfunction "PC10_43") (pintype "bidirectional"))
    )
    (net (code "127") (name "Net-(U1-PD0)") (class "Default")
      (node (ref "TP14") (pin "TP") (pinfunction "TP_TP") (pintype "input"))
      (node (ref "U1") (pin "28") (pinfunction "PD0_28") (pintype "bidirectional"))
    )
    (net (code "128") (name "Net-(U1-PD1)") (class "Default")
      (node (ref "TP13") (pin "TP") (pinfunction "TP_TP") (pintype "input"))
      (node (ref "U1") (pin "29") (pinfunction "PD1_29") (pintype "bidirectional"))
    )
    (net (code "129") (name "Net-(U1-PD2)") (class "Default")
      (node (ref "TP12") (pin "TP") (pinfunction "TP_TP") (pintype "input"))
      (node (ref "U1") (pin "30") (pinfunction "PD2_30") (pintype "bidirectional"))
    )
    (net (code "130") (name "Net-(U1-PD3)") (class "Default")
      (node (ref "TP11") (pin "TP") (pinfunction "TP_TP") (pintype "input"))
      (node (ref "U1") (pin "31") (pinfunction "PD3_31") (pintype "bidirectional"))
    )
    (net (code "131") (name "Net-(U1-PD4)") (class "Default")
      (node (ref "TP10") (pin "TP") (pinfunction "TP_TP") (pintype "input"))
      (node (ref "U1") (pin "32") (pinfunction "PD4_32") (pintype "bidirectional"))
    )
    (net (code "132") (name "Net-(U1-PD5)") (class "Default")
      (node (ref "CAPS") (pin "C") (pinfunction "C_C") (pintype "passive"))
      (node (ref "U1") (pin "33") (pinfunction "PD5_33") (pintype "bidirectional"))
    )
    (net (code "133") (name "Net-(U1-PD6)") (class "Default")
      (node (ref "SCROLL") (pin "C") (pinfunction "C_C") (pintype "passive"))
      (node (ref "U1") (pin "34") (pinfunction "PD6_34") (pintype "bidirectional"))
    )
    (net (code "134") (name "Net-(U1-PD7)") (class "Default")
      (node (ref "LED1\\") (pin "C") (pinfunction "C_C") (pintype "passive"))
      (node (ref "U1") (pin "35") (pinfunction "PD7_35") (pintype "bidirectional"))
    )
    (net (code "135") (name "Net-(U1-PD8)") (class "Default")
      (node (ref "TP9") (pin "TP") (pinfunction "TP_TP") (pintype "input"))
      (node (ref "U1") (pin "36") (pinfunction "PD8_36") (pintype "bidirectional"))
    )
    (net (code "136") (name "Net-(U1-PF5)") (class "Default")
      (node (ref "TP18") (pin "TP") (pinfunction "TP_TP") (pintype "input"))
      (node (ref "U1") (pin "54") (pinfunction "PF5_54") (pintype "bidirectional"))
    )
    (net (code "137") (name "Net-(U1-PF10)") (class "Default")
      (node (ref "R1") (pin "1") (pinfunction "1_1") (pintype "passive"))
      (node (ref "U1") (pin "47") (pinfunction "PF10_47") (pintype "bidirectional"))
    )
    (net (code "138") (name "Net-(U1-PF11)") (class "Default")
      (node (ref "R2") (pin "1") (pinfunction "1_1") (pintype "passive"))
      (node (ref "U1") (pin "48") (pinfunction "PF11_48") (pintype "bidirectional"))
    )
    (net (code "139") (name "Net-(U1-PF12)") (class "Default")
      (node (ref "TP17") (pin "TP") (pinfunction "TP_TP") (pintype "input"))
      (node (ref "U1") (pin "53") (pinfunction "PF12_53") (pintype "bidirectional"))
    )
    (net (code "140") (name "Net-(U2-CC)") (class "Default")
      (node (ref "C17") (pin "1") (pinfunction "1_1") (pintype "passive"))
      (node (ref "U2") (pin "6") (pinfunction "CC_6") (pintype "bidirectional"))
    )
    (net (code "141") (name "Net-(U2-FAULT)") (class "Default")
      (node (ref "R6") (pin "1") (pinfunction "1_1") (pintype "passive"))
      (node (ref "U2") (pin "8") (pinfunction "FAULT_8") (pintype "bidirectional"))
    )
    (net (code "142") (name "R1") (class "Default")
      (node (ref "D1") (pin "1") (pinfunction "1_1") (pintype "bidirectional"))
      (node (ref "D13") (pin "1") (pinfunction "1_1") (pintype "bidirectional"))
      (node (ref "D19") (pin "1") (pinfunction "1_1") (pintype "bidirectional"))
      (node (ref "D25") (pin "1") (pinfunction "1_1") (pintype "bidirectional"))
      (node (ref "D31") (pin "1") (pinfunction "1_1") (pintype "bidirectional"))
      (node (ref "D37") (pin "1") (pinfunction "1_1") (pintype "bidirectional"))
      (node (ref "D43") (pin "1") (pinfunction "1_1") (pintype "bidirectional"))
      (node (ref "D49") (pin "1") (pinfunction "1_1") (pintype "bidirectional"))
      (node (ref "D55") (pin "1") (pinfunction "1_1") (pintype "bidirectional"))
      (node (ref "D61") (pin "1") (pinfunction "1_1") (pintype "bidirectional"))
      (node (ref "D67") (pin "1") (pinfunction "1_1") (pintype "bidirectional"))
      (node (ref "D7") (pin "1") (pinfunction "1_1") (pintype "bidirectional"))
      (node (ref "D72") (pin "1") (pinfunction "1_1") (pintype "bidirectional"))
      (node (ref "D77") (pin "1") (pinfunction "1_1") (pintype "bidirectional"))
      (node (ref "D82") (pin "1") (pinfunction "1_1") (pintype "bidirectional"))
      (node (ref "D85") (pin "1") (pinfunction "1_1") (pintype "bidirectional"))
      (node (ref "D88") (pin "1") (pinfunction "1_1") (pintype "bidirectional"))
      (node (ref "U1") (pin "1") (pinfunction "PA0_1") (pintype "bidirectional"))
    )
    (net (code "143") (name "R2") (class "Default")
      (node (ref "D14") (pin "1") (pinfunction "1_1") (pintype "bidirectional"))
      (node (ref "D2") (pin "1") (pinfunction "1_1") (pintype "bidirectional"))
      (node (ref "D20") (pin "1") (pinfunction "1_1") (pintype "bidirectional"))
      (node (ref "D26") (pin "1") (pinfunction "1_1") (pintype "bidirectional"))
      (node (ref "D32") (pin "1") (pinfunction "1_1") (pintype "bidirectional"))
      (node (ref "D38") (pin "1") (pinfunction "1_1") (pintype "bidirectional"))
      (node (ref "D44") (pin "1") (pinfunction "1_1") (pintype "bidirectional"))
      (node (ref "D50") (pin "1") (pinfunction "1_1") (pintype "bidirectional"))
      (node (ref "D56") (pin "1") (pinfunction "1_1") (pintype "bidirectional"))
      (node (ref "D62") (pin "1") (pinfunction "1_1") (pintype "bidirectional"))
      (node (ref "D68") (pin "1") (pinfunction "1_1") (pintype "bidirectional"))
      (node (ref "D73") (pin "1") (pinfunction "1_1") (pintype "bidirectional"))
      (node (ref "D78") (pin "1") (pinfunction "1_1") (pintype "bidirectional"))
      (node (ref "D8") (pin "1") (pinfunction "1_1") (pintype "bidirectional"))
      (node (ref "D83") (pin "1") (pinfunction "1_1") (pintype "bidirectional"))
      (node (ref "D86") (pin "1") (pinfunction "1_1") (pintype "bidirectional"))
      (node (ref "D89") (pin "1") (pinfunction "1_1") (pintype "bidirectional"))
      (node (ref "D91") (pin "1") (pinfunction "1_1") (pintype "bidirectional"))
      (node (ref "U1") (pin "2") (pinfunction "PA1_2") (pintype "bidirectional"))
    )
    (net (code "144") (name "R3") (class "Default")
      (node (ref "D15") (pin "1") (pinfunction "1_1") (pintype "bidirectional"))
      (node (ref "D21") (pin "1") (pinfunction "1_1") (pintype "bidirectional"))
      (node (ref "D27") (pin "1") (pinfunction "1_1") (pintype "bidirectional"))
      (node (ref "D3") (pin "1") (pinfunction "1_1") (pintype "bidirectional"))
      (node (ref "D33") (pin "1") (pinfunction "1_1") (pintype "bidirectional"))
      (node (ref "D39") (pin "1") (pinfunction "1_1") (pintype "bidirectional"))
      (node (ref "D45") (pin "1") (pinfunction "1_1") (pintype "bidirectional"))
      (node (ref "D51") (pin "1") (pinfunction "1_1") (pintype "bidirectional"))
      (node (ref "D57") (pin "1") (pinfunction "1_1") (pintype "bidirectional"))
      (node (ref "D63") (pin "1") (pinfunction "1_1") (pintype "bidirectional"))
      (node (ref "D69") (pin "1") (pinfunction "1_1") (pintype "bidirectional"))
      (node (ref "D74") (pin "1") (pinfunction "1_1") (pintype "bidirectional"))
      (node (ref "D79") (pin "1") (pinfunction "1_1") (pintype "bidirectional"))
      (node (ref "D84") (pin "1") (pinfunction "1_1") (pintype "bidirectional"))
      (node (ref "D87") (pin "1") (pinfunction "1_1") (pintype "bidirectional"))
      (node (ref "D9") (pin "1") (pinfunction "1_1") (pintype "bidirectional"))
      (node (ref "D90") (pin "1") (pinfunction "1_1") (pintype "bidirectional"))
      (node (ref "D92") (pin "1") (pinfunction "1_1") (pintype "bidirectional"))
      (node (ref "U1") (pin "3") (pinfunction "PA2_3") (pintype "bidirectional"))
    )
    (net (code "145") (name "R4") (class "Default")
      (node (ref "D10") (pin "1") (pinfunction "1_1") (pintype "bidirectional"))
      (node (ref "D16") (pin "1") (pinfunction "1_1") (pintype "bidirectional"))
      (node (ref "D22") (pin "1") (pinfunction "1_1") (pintype "bidirectional"))
      (node (ref "D28") (pin "1") (pinfunction "1_1") (pintype "bidirectional"))
      (node (ref "D34") (pin "1") (pinfunction "1_1") (pintype "bidirectional"))
      (node (ref "D4") (pin "1") (pinfunction "1_1") (pintype "bidirectional"))
      (node (ref "D40") (pin "1") (pinfunction "1_1") (pintype "bidirectional"))
      (node (ref "D46") (pin "1") (pinfunction "1_1") (pintype "bidirectional"))
      (node (ref "D52") (pin "1") (pinfunction "1_1") (pintype "bidirectional"))
      (node (ref "D58") (pin "1") (pinfunction "1_1") (pintype "bidirectional"))
      (node (ref "D64") (pin "1") (pinfunction "1_1") (pintype "bidirectional"))
      (node (ref "D70") (pin "1") (pinfunction "1_1") (pintype "bidirectional"))
      (node (ref "D75") (pin "1") (pinfunction "1_1") (pintype "bidirectional"))
      (node (ref "D80") (pin "1") (pinfunction "1_1") (pintype "bidirectional"))
      (node (ref "U1") (pin "4") (pinfunction "PA3_4") (pintype "bidirectional"))
    )
    (net (code "146") (name "R5") (class "Default")
      (node (ref "D11") (pin "1") (pinfunction "1_1") (pintype "bidirectional"))
      (node (ref "D17") (pin "1") (pinfunction "1_1") (pintype "bidirectional"))
      (node (ref "D23") (pin "1") (pinfunction "1_1") (pintype "bidirectional"))
      (node (ref "D29") (pin "1") (pinfunction "1_1") (pintype "bidirectional"))
      (node (ref "D35") (pin "1") (pinfunction "1_1") (pintype "bidirectional"))
      (node (ref "D41") (pin "1") (pinfunction "1_1") (pintype "bidirectional"))
      (node (ref "D47") (pin "1") (pinfunction "1_1") (pintype "bidirectional"))
      (node (ref "D5") (pin "1") (pinfunction "1_1") (pintype "bidirectional"))
      (node (ref "D53") (pin "1") (pinfunction "1_1") (pintype "bidirectional"))
      (node (ref "D59") (pin "1") (pinfunction "1_1") (pintype "bidirectional"))
      (node (ref "D65") (pin "1") (pinfunction "1_1") (pintype "bidirectional"))
      (node (ref "D71") (pin "1") (pinfunction "1_1") (pintype "bidirectional"))
      (node (ref "D76") (pin "1") (pinfunction "1_1") (pintype "bidirectional"))
      (node (ref "D81") (pin "1") (pinfunction "1_1") (pintype "bidirectional"))
      (node (ref "U1") (pin "5") (pinfunction "PA4_5") (pintype "bidirectional"))
    )
    (net (code "147") (name "R6") (class "Default")
      (node (ref "D12") (pin "1") (pinfunction "1_1") (pintype "bidirectional"))
      (node (ref "D18") (pin "1") (pinfunction "1_1") (pintype "bidirectional"))
      (node (ref "D24") (pin "1") (pinfunction "1_1") (pintype "bidirectional"))
      (node (ref "D30") (pin "1") (pinfunction "1_1") (pintype "bidirectional"))
      (node (ref "D36") (pin "1") (pinfunction "1_1") (pintype "bidirectional"))
      (node (ref "D42") (pin "1") (pinfunction "1_1") (pintype "bidirectional"))
      (node (ref "D48") (pin "1") (pinfunction "1_1") (pintype "bidirectional"))
      (node (ref "D54") (pin "1") (pinfunction "1_1") (pintype "bidirectional"))
      (node (ref "D6") (pin "1") (pinfunction "1_1") (pintype "bidirectional"))
      (node (ref "D60") (pin "1") (pinfunction "1_1") (pintype "bidirectional"))
      (node (ref "D66") (pin "1") (pinfunction "1_1") (pintype "bidirectional"))
      (node (ref "U1") (pin "6") (pinfunction "PA5_6") (pintype "bidirectional"))
    )
    (net (code "148") (name "RESET") (class "Default")
      (node (ref "ARM_20_HEADER") (pin "15") (pinfunction "15_15") (pintype "passive"))
      (node (ref "SJ2") (pin "1") (pinfunction "1_1") (pintype "passive"))
      (node (ref "U1") (pin "20") (pinfunction "RESETN_20") (pintype "bidirectional"))
    )
    (net (code "149") (name "RESETB") (class "Default")
      (node (ref "SILABS_DEBUG") (pin "10") (pinfunction "10_10") (pintype "passive"))
      (node (ref "SJ2") (pin "2") (pinfunction "2_2") (pintype "passive"))
    )
    (net (code "150") (name "SWCLK") (class "Default")
      (node (ref "ARM_20_HEADER") (pin "9") (pinfunction "9_9") (pintype "passive"))
      (node (ref "SILABS_DEBUG") (pin "4") (pinfunction "4_4") (pintype "passive"))
      (node (ref "U1") (pin "49") (pinfunction "PF0_49") (pintype "bidirectional"))
    )
    (net (code "151") (name "SWDIO") (class "Default")
      (node (ref "ARM_20_HEADER") (pin "7") (pinfunction "7_7") (pintype "passive"))
      (node (ref "SILABS_DEBUG") (pin "2") (pinfunction "2_2") (pintype "passive"))
      (node (ref "U1") (pin "50") (pinfunction "PF1_50") (pintype "bidirectional"))
    )
    (net (code "152") (name "SWO") (class "Default")
      (node (ref "ARM_20_HEADER") (pin "13") (pinfunction "13_13") (pintype "passive"))
      (node (ref "SILABS_DEBUG") (pin "6") (pinfunction "6_6") (pintype "passive"))
      (node (ref "U1") (pin "51") (pinfunction "PF2_51") (pintype "bidirectional"))
    )
    (net (code "153") (name "TDI") (class "Default")
      (node (ref "SILABS_DEBUG") (pin "8") (pinfunction "8_8") (pintype "passive"))
      (node (ref "TP6") (pin "TP") (pinfunction "TP_TP") (pintype "input"))
      (node (ref "U1") (pin "44") (pinfunction "PC11_44") (pintype "bidirectional"))
    )
    (net (code "154") (name "USB1_N") (class "Default")
      (node (ref "J1") (pin "D-") (pinfunction "D-_D-") (pintype "bidirectional"))
      (node (ref "R1") (pin "2") (pinfunction "2_2") (pintype "passive"))
    )
    (net (code "155") (name "USB1_P") (class "Default")
      (node (ref "J1") (pin "D+") (pinfunction "D+_D+") (pintype "bidirectional"))
      (node (ref "R2") (pin "2") (pinfunction "2_2") (pintype "passive"))
    )
    (net (code "156") (name "VBUS1") (class "Default")
      (node (ref "C12") (pin "1") (pinfunction "1_1") (pintype "passive"))
      (node (ref "C16") (pin "1") (pinfunction "1_1") (pintype "passive"))
      (node (ref "J1") (pin "VBUS") (pinfunction "VBUS_VBUS") (pintype "bidirectional"))
      (node (ref "U1") (pin "45") (pinfunction "USB_VREG_I_45") (pintype "bidirectional"))
      (node (ref "U1") (pin "52") (pinfunction "USB_VBUS_52") (pintype "bidirectional"))
      (node (ref "U2") (pin "2") (pinfunction "IN_2") (pintype "bidirectional"))
      (node (ref "U2") (pin "7") (pinfunction "SHDN_7") (pintype "bidirectional"))
    )
    (net (code "157") (name "VCC3V3") (class "Default")
      (node (ref "C1") (pin "1") (pinfunction "1_1") (pintype "passive"))
      (node (ref "C10") (pin "1") (pinfunction "1_1") (pintype "passive"))
      (node (ref "C11") (pin "1") (pinfunction "1_1") (pintype "passive"))
      (node (ref "C13") (pin "1") (pinfunction "1_1") (pintype "passive"))
      (node (ref "C18") (pin "1") (pinfunction "1_1") (pintype "passive"))
      (node (ref "C2") (pin "1") (pinfunction "1_1") (pintype "passive"))
      (node (ref "C4") (pin "1") (pinfunction "1_1") (pintype "passive"))
      (node (ref "C5") (pin "1") (pinfunction "1_1") (pintype "passive"))
      (node (ref "C6") (pin "1") (pinfunction "1_1") (pintype "passive"))
      (node (ref "C7") (pin "1") (pinfunction "1_1") (pintype "passive"))
      (node (ref "C8") (pin "1") (pinfunction "1_1") (pintype "passive"))
      (node (ref "C9") (pin "1") (pinfunction "1_1") (pintype "passive"))
      (node (ref "R3") (pin "1") (pinfunction "1_1") (pintype "passive"))
      (node (ref "R4") (pin "1") (pinfunction "1_1") (pintype "passive"))
      (node (ref "R5") (pin "1") (pinfunction "1_1") (pintype "passive"))
      (node (ref "R6") (pin "2") (pinfunction "2_2") (pintype "passive"))
      (node (ref "SILABS_DEBUG") (pin "1") (pinfunction "1_1") (pintype "passive"))
      (node (ref "SJ1") (pin "3") (pinfunction "3_3") (pintype "passive"))
      (node (ref "U1") (pin "23") (pinfunction "AVDD_1_23") (pintype "bidirectional"))
      (node (ref "U1") (pin "26") (pinfunction "IO_VDD_3_26") (pintype "bidirectional"))
      (node (ref "U1") (pin "27") (pinfunction "AVDD_0_27") (pintype "bidirectional"))
      (node (ref "U1") (pin "39") (pinfunction "VDD_DREG_39") (pintype "bidirectional"))
      (node (ref "U1") (pin "55") (pinfunction "IOVDD_5_55") (pintype "bidirectional"))
      (node (ref "U1") (pin "7") (pinfunction "IOVDD_0_7") (pintype "bidirectional"))
      (node (ref "U2") (pin "1") (pinfunction "OUT_1") (pintype "bidirectional"))
      (node (ref "U2") (pin "4") (pinfunction "OUT_4") (pintype "bidirectional"))
    )
    (net (code "158") (name "VREG_OUT") (class "Default")
      (node (ref "SJ1") (pin "2") (pinfunction "2_2") (pintype "passive"))
      (node (ref "U1") (pin "46") (pinfunction "USB_VREG_O_46") (pintype "bidirectional"))
    )
    (net (code "159") (name "V_TARGET") (class "Default")
      (node (ref "ARM_20_HEADER") (pin "1") (pinfunction "1_1") (pintype "passive"))
    )
    (net (code "160") (name "unconnected-(ARM_20_HEADER-Pad2)") (class "Default")
      (node (ref "ARM_20_HEADER") (pin "2") (pinfunction "2_2") (pintype "passive"))
    )
    (net (code "161") (name "unconnected-(ARM_20_HEADER-Pad3)") (class "Default")
      (node (ref "ARM_20_HEADER") (pin "3") (pinfunction "3_3") (pintype "passive"))
    )
    (net (code "162") (name "unconnected-(ARM_20_HEADER-Pad5)") (class "Default")
      (node (ref "ARM_20_HEADER") (pin "5") (pinfunction "5_5") (pintype "passive"))
    )
    (net (code "163") (name "unconnected-(ARM_20_HEADER-Pad11)") (class "Default")
      (node (ref "ARM_20_HEADER") (pin "11") (pinfunction "11_11") (pintype "passive"))
    )
    (net (code "164") (name "unconnected-(ARM_20_HEADER-Pad17)") (class "Default")
      (node (ref "ARM_20_HEADER") (pin "17") (pinfunction "17_17") (pintype "passive"))
    )
    (net (code "165") (name "unconnected-(ARM_20_HEADER-Pad19)") (class "Default")
      (node (ref "ARM_20_HEADER") (pin "19") (pinfunction "19_19") (pintype "passive"))
    )
    (net (code "166") (name "unconnected-(J1-GND-PadS1)") (class "Default")
      (node (ref "J1") (pin "S1") (pinfunction "GND_S1") (pintype "bidirectional"))
    )
    (net (code "167") (name "unconnected-(J1-GND-PadS2)") (class "Default")
      (node (ref "J1") (pin "S2") (pinfunction "GND_S2") (pintype "bidirectional"))
    )
    (net (code "168") (name "unconnected-(SILABS_DEBUG-Pad7)") (class "Default")
      (node (ref "SILABS_DEBUG") (pin "7") (pinfunction "7_7") (pintype "passive"))
    )
    (net (code "169") (name "unconnected-(SPACE-PadA)") (class "Default")
      (node (ref "SPACE") (pin "A") (pinfunction "A_A") (pintype "bidirectional"))
    )
    (net (code "170") (name "unconnected-(SPACE-PadK)") (class "Default")
      (node (ref "SPACE") (pin "K") (pinfunction "K_K") (pintype "bidirectional"))
    )
    (net (code "171") (name "unconnected-(SW1-PadA)") (class "Default")
      (node (ref "SW1") (pin "A") (pinfunction "A_A") (pintype "bidirectional"))
    )
    (net (code "172") (name "unconnected-(SW1-PadK)") (class "Default")
      (node (ref "SW1") (pin "K") (pinfunction "K_K") (pintype "bidirectional"))
    )
    (net (code "173") (name "unconnected-(SW2-PadA)") (class "Default")
      (node (ref "SW2") (pin "A") (pinfunction "A_A") (pintype "bidirectional"))
    )
    (net (code "174") (name "unconnected-(SW2-PadK)") (class "Default")
      (node (ref "SW2") (pin "K") (pinfunction "K_K") (pintype "bidirectional"))
    )
    (net (code "175") (name "unconnected-(SW3-PadA)") (class "Default")
      (node (ref "SW3") (pin "A") (pinfunction "A_A") (pintype "bidirectional"))
    )
    (net (code "176") (name "unconnected-(SW3-PadK)") (class "Default")
      (node (ref "SW3") (pin "K") (pinfunction "K_K") (pintype "bidirectional"))
    )
    (net (code "177") (name "unconnected-(SW4-PadA)") (class "Default")
      (node (ref "SW4") (pin "A") (pinfunction "A_A") (pintype "bidirectional"))
    )
    (net (code "178") (name "unconnected-(SW4-PadK)") (class "Default")
      (node (ref "SW4") (pin "K") (pinfunction "K_K") (pintype "bidirectional"))
    )
    (net (code "179") (name "unconnected-(SW5-PadA)") (class "Default")
      (node (ref "SW5") (pin "A") (pinfunction "A_A") (pintype "bidirectional"))
    )
    (net (code "180") (name "unconnected-(SW5-PadK)") (class "Default")
      (node (ref "SW5") (pin "K") (pinfunction "K_K") (pintype "bidirectional"))
    )
    (net (code "181") (name "unconnected-(SW6-PadA)") (class "Default")
      (node (ref "SW6") (pin "A") (pinfunction "A_A") (pintype "bidirectional"))
    )
    (net (code "182") (name "unconnected-(SW6-PadK)") (class "Default")
      (node (ref "SW6") (pin "K") (pinfunction "K_K") (pintype "bidirectional"))
    )
    (net (code "183") (name "unconnected-(SW7-PadA)") (class "Default")
      (node (ref "SW7") (pin "A") (pinfunction "A_A") (pintype "bidirectional"))
    )
    (net (code "184") (name "unconnected-(SW7-PadK)") (class "Default")
      (node (ref "SW7") (pin "K") (pinfunction "K_K") (pintype "bidirectional"))
    )
    (net (code "185") (name "unconnected-(SW8-PadA)") (class "Default")
      (node (ref "SW8") (pin "A") (pinfunction "A_A") (pintype "bidirectional"))
    )
    (net (code "186") (name "unconnected-(SW8-PadK)") (class "Default")
      (node (ref "SW8") (pin "K") (pinfunction "K_K") (pintype "bidirectional"))
    )
    (net (code "187") (name "unconnected-(SW9-PadA)") (class "Default")
      (node (ref "SW9") (pin "A") (pinfunction "A_A") (pintype "bidirectional"))
    )
    (net (code "188") (name "unconnected-(SW9-PadK)") (class "Default")
      (node (ref "SW9") (pin "K") (pinfunction "K_K") (pintype "bidirectional"))
    )
    (net (code "189") (name "unconnected-(SW10-PadA)") (class "Default")
      (node (ref "SW10") (pin "A") (pinfunction "A_A") (pintype "bidirectional"))
    )
    (net (code "190") (name "unconnected-(SW10-PadK)") (class "Default")
      (node (ref "SW10") (pin "K") (pinfunction "K_K") (pintype "bidirectional"))
    )
    (net (code "191") (name "unconnected-(SW11-PadA)") (class "Default")
      (node (ref "SW11") (pin "A") (pinfunction "A_A") (pintype "bidirectional"))
    )
    (net (code "192") (name "unconnected-(SW11-PadK)") (class "Default")
      (node (ref "SW11") (pin "K") (pinfunction "K_K") (pintype "bidirectional"))
    )
    (net (code "193") (name "unconnected-(SW12-PadA)") (class "Default")
      (node (ref "SW12") (pin "A") (pinfunction "A_A") (pintype "bidirectional"))
    )
    (net (code "194") (name "unconnected-(SW12-PadK)") (class "Default")
      (node (ref "SW12") (pin "K") (pinfunction "K_K") (pintype "bidirectional"))
    )
    (net (code "195") (name "unconnected-(SW13-PadA)") (class "Default")
      (node (ref "SW13") (pin "A") (pinfunction "A_A") (pintype "bidirectional"))
    )
    (net (code "196") (name "unconnected-(SW13-PadK)") (class "Default")
      (node (ref "SW13") (pin "K") (pinfunction "K_K") (pintype "bidirectional"))
    )
    (net (code "197") (name "unconnected-(SW14-PadA)") (class "Default")
      (node (ref "SW14") (pin "A") (pinfunction "A_A") (pintype "bidirectional"))
    )
    (net (code "198") (name "unconnected-(SW14-PadK)") (class "Default")
      (node (ref "SW14") (pin "K") (pinfunction "K_K") (pintype "bidirectional"))
    )
    (net (code "199") (name "unconnected-(SW15-PadA)") (class "Default")
      (node (ref "SW15") (pin "A") (pinfunction "A_A") (pintype "bidirectional"))
    )
    (net (code "200") (name "unconnected-(SW15-PadK)") (class "Default")
      (node (ref "SW15") (pin "K") (pinfunction "K_K") (pintype "bidirectional"))
    )
    (net (code "201") (name "unconnected-(SW16-PadA)") (class "Default")
      (node (ref "SW16") (pin "A") (pinfunction "A_A") (pintype "bidirectional"))
    )
    (net (code "202") (name "unconnected-(SW16-PadK)") (class "Default")
      (node (ref "SW16") (pin "K") (pinfunction "K_K") (pintype "bidirectional"))
    )
    (net (code "203") (name "unconnected-(SW17-PadA)") (class "Default")
      (node (ref "SW17") (pin "A") (pinfunction "A_A") (pintype "bidirectional"))
    )
    (net (code "204") (name "unconnected-(SW17-PadK)") (class "Default")
      (node (ref "SW17") (pin "K") (pinfunction "K_K") (pintype "bidirectional"))
    )
    (net (code "205") (name "unconnected-(SW18-PadA)") (class "Default")
      (node (ref "SW18") (pin "A") (pinfunction "A_A") (pintype "bidirectional"))
    )
    (net (code "206") (name "unconnected-(SW18-PadK)") (class "Default")
      (node (ref "SW18") (pin "K") (pinfunction "K_K") (pintype "bidirectional"))
    )
    (net (code "207") (name "unconnected-(SW19-PadA)") (class "Default")
      (node (ref "SW19") (pin "A") (pinfunction "A_A") (pintype "bidirectional"))
    )
    (net (code "208") (name "unconnected-(SW19-PadK)") (class "Default")
      (node (ref "SW19") (pin "K") (pinfunction "K_K") (pintype "bidirectional"))
    )
    (net (code "209") (name "unconnected-(SW20-PadA)") (class "Default")
      (node (ref "SW20") (pin "A") (pinfunction "A_A") (pintype "bidirectional"))
    )
    (net (code "210") (name "unconnected-(SW20-PadK)") (class "Default")
      (node (ref "SW20") (pin "K") (pinfunction "K_K") (pintype "bidirectional"))
    )
    (net (code "211") (name "unconnected-(SW21-PadA)") (class "Default")
      (node (ref "SW21") (pin "A") (pinfunction "A_A") (pintype "bidirectional"))
    )
    (net (code "212") (name "unconnected-(SW21-PadK)") (class "Default")
      (node (ref "SW21") (pin "K") (pinfunction "K_K") (pintype "bidirectional"))
    )
    (net (code "213") (name "unconnected-(SW22-PadA)") (class "Default")
      (node (ref "SW22") (pin "A") (pinfunction "A_A") (pintype "bidirectional"))
    )
    (net (code "214") (name "unconnected-(SW22-PadK)") (class "Default")
      (node (ref "SW22") (pin "K") (pinfunction "K_K") (pintype "bidirectional"))
    )
    (net (code "215") (name "unconnected-(SW23-PadA)") (class "Default")
      (node (ref "SW23") (pin "A") (pinfunction "A_A") (pintype "bidirectional"))
    )
    (net (code "216") (name "unconnected-(SW23-PadK)") (class "Default")
      (node (ref "SW23") (pin "K") (pinfunction "K_K") (pintype "bidirectional"))
    )
    (net (code "217") (name "unconnected-(SW24-PadA)") (class "Default")
      (node (ref "SW24") (pin "A") (pinfunction "A_A") (pintype "bidirectional"))
    )
    (net (code "218") (name "unconnected-(SW24-PadK)") (class "Default")
      (node (ref "SW24") (pin "K") (pinfunction "K_K") (pintype "bidirectional"))
    )
    (net (code "219") (name "unconnected-(SW25-PadA)") (class "Default")
      (node (ref "SW25") (pin "A") (pinfunction "A_A") (pintype "bidirectional"))
    )
    (net (code "220") (name "unconnected-(SW25-PadK)") (class "Default")
      (node (ref "SW25") (pin "K") (pinfunction "K_K") (pintype "bidirectional"))
    )
    (net (code "221") (name "unconnected-(SW26-PadA)") (class "Default")
      (node (ref "SW26") (pin "A") (pinfunction "A_A") (pintype "bidirectional"))
    )
    (net (code "222") (name "unconnected-(SW26-PadK)") (class "Default")
      (node (ref "SW26") (pin "K") (pinfunction "K_K") (pintype "bidirectional"))
    )
    (net (code "223") (name "unconnected-(SW27-PadA)") (class "Default")
      (node (ref "SW27") (pin "A") (pinfunction "A_A") (pintype "bidirectional"))
    )
    (net (code "224") (name "unconnected-(SW27-PadK)") (class "Default")
      (node (ref "SW27") (pin "K") (pinfunction "K_K") (pintype "bidirectional"))
    )
    (net (code "225") (name "unconnected-(SW28-PadA)") (class "Default")
      (node (ref "SW28") (pin "A") (pinfunction "A_A") (pintype "bidirectional"))
    )
    (net (code "226") (name "unconnected-(SW28-PadK)") (class "Default")
      (node (ref "SW28") (pin "K") (pinfunction "K_K") (pintype "bidirectional"))
    )
    (net (code "227") (name "unconnected-(SW29-PadA)") (class "Default")
      (node (ref "SW29") (pin "A") (pinfunction "A_A") (pintype "bidirectional"))
    )
    (net (code "228") (name "unconnected-(SW29-PadK)") (class "Default")
      (node (ref "SW29") (pin "K") (pinfunction "K_K") (pintype "bidirectional"))
    )
    (net (code "229") (name "unconnected-(SW30-PadA)") (class "Default")
      (node (ref "SW30") (pin "A") (pinfunction "A_A") (pintype "bidirectional"))
    )
    (net (code "230") (name "unconnected-(SW30-PadK)") (class "Default")
      (node (ref "SW30") (pin "K") (pinfunction "K_K") (pintype "bidirectional"))
    )
    (net (code "231") (name "unconnected-(SW31-PadA)") (class "Default")
      (node (ref "SW31") (pin "A") (pinfunction "A_A") (pintype "bidirectional"))
    )
    (net (code "232") (name "unconnected-(SW31-PadK)") (class "Default")
      (node (ref "SW31") (pin "K") (pinfunction "K_K") (pintype "bidirectional"))
    )
    (net (code "233") (name "unconnected-(SW32-PadA)") (class "Default")
      (node (ref "SW32") (pin "A") (pinfunction "A_A") (pintype "bidirectional"))
    )
    (net (code "234") (name "unconnected-(SW32-PadK)") (class "Default")
      (node (ref "SW32") (pin "K") (pinfunction "K_K") (pintype "bidirectional"))
    )
    (net (code "235") (name "unconnected-(SW33-PadA)") (class "Default")
      (node (ref "SW33") (pin "A") (pinfunction "A_A") (pintype "bidirectional"))
    )
    (net (code "236") (name "unconnected-(SW33-PadK)") (class "Default")
      (node (ref "SW33") (pin "K") (pinfunction "K_K") (pintype "bidirectional"))
    )
    (net (code "237") (name "unconnected-(SW34-PadA)") (class "Default")
      (node (ref "SW34") (pin "A") (pinfunction "A_A") (pintype "bidirectional"))
    )
    (net (code "238") (name "unconnected-(SW34-PadK)") (class "Default")
      (node (ref "SW34") (pin "K") (pinfunction "K_K") (pintype "bidirectional"))
    )
    (net (code "239") (name "unconnected-(SW35-PadA)") (class "Default")
      (node (ref "SW35") (pin "A") (pinfunction "A_A") (pintype "bidirectional"))
    )
    (net (code "240") (name "unconnected-(SW35-PadK)") (class "Default")
      (node (ref "SW35") (pin "K") (pinfunction "K_K") (pintype "bidirectional"))
    )
    (net (code "241") (name "unconnected-(SW36-PadA)") (class "Default")
      (node (ref "SW36") (pin "A") (pinfunction "A_A") (pintype "bidirectional"))
    )
    (net (code "242") (name "unconnected-(SW36-PadK)") (class "Default")
      (node (ref "SW36") (pin "K") (pinfunction "K_K") (pintype "bidirectional"))
    )
    (net (code "243") (name "unconnected-(SW37-PadA)") (class "Default")
      (node (ref "SW37") (pin "A") (pinfunction "A_A") (pintype "bidirectional"))
    )
    (net (code "244") (name "unconnected-(SW37-PadK)") (class "Default")
      (node (ref "SW37") (pin "K") (pinfunction "K_K") (pintype "bidirectional"))
    )
    (net (code "245") (name "unconnected-(SW38-PadA)") (class "Default")
      (node (ref "SW38") (pin "A") (pinfunction "A_A") (pintype "bidirectional"))
    )
    (net (code "246") (name "unconnected-(SW38-PadK)") (class "Default")
      (node (ref "SW38") (pin "K") (pinfunction "K_K") (pintype "bidirectional"))
    )
    (net (code "247") (name "unconnected-(SW39-PadA)") (class "Default")
      (node (ref "SW39") (pin "A") (pinfunction "A_A") (pintype "bidirectional"))
    )
    (net (code "248") (name "unconnected-(SW39-PadK)") (class "Default")
      (node (ref "SW39") (pin "K") (pinfunction "K_K") (pintype "bidirectional"))
    )
    (net (code "249") (name "unconnected-(SW40-PadA)") (class "Default")
      (node (ref "SW40") (pin "A") (pinfunction "A_A") (pintype "bidirectional"))
    )
    (net (code "250") (name "unconnected-(SW40-PadK)") (class "Default")
      (node (ref "SW40") (pin "K") (pinfunction "K_K") (pintype "bidirectional"))
    )
    (net (code "251") (name "unconnected-(SW41-PadA)") (class "Default")
      (node (ref "SW41") (pin "A") (pinfunction "A_A") (pintype "bidirectional"))
    )
    (net (code "252") (name "unconnected-(SW41-PadK)") (class "Default")
      (node (ref "SW41") (pin "K") (pinfunction "K_K") (pintype "bidirectional"))
    )
    (net (code "253") (name "unconnected-(SW42-PadA)") (class "Default")
      (node (ref "SW42") (pin "A") (pinfunction "A_A") (pintype "bidirectional"))
    )
    (net (code "254") (name "unconnected-(SW42-PadK)") (class "Default")
      (node (ref "SW42") (pin "K") (pinfunction "K_K") (pintype "bidirectional"))
    )
    (net (code "255") (name "unconnected-(SW43-PadA)") (class "Default")
      (node (ref "SW43") (pin "A") (pinfunction "A_A") (pintype "bidirectional"))
    )
    (net (code "256") (name "unconnected-(SW43-PadK)") (class "Default")
      (node (ref "SW43") (pin "K") (pinfunction "K_K") (pintype "bidirectional"))
    )
    (net (code "257") (name "unconnected-(SW44-PadA)") (class "Default")
      (node (ref "SW44") (pin "A") (pinfunction "A_A") (pintype "bidirectional"))
    )
    (net (code "258") (name "unconnected-(SW44-PadK)") (class "Default")
      (node (ref "SW44") (pin "K") (pinfunction "K_K") (pintype "bidirectional"))
    )
    (net (code "259") (name "unconnected-(SW45-PadA)") (class "Default")
      (node (ref "SW45") (pin "A") (pinfunction "A_A") (pintype "bidirectional"))
    )
    (net (code "260") (name "unconnected-(SW45-PadK)") (class "Default")
      (node (ref "SW45") (pin "K") (pinfunction "K_K") (pintype "bidirectional"))
    )
    (net (code "261") (name "unconnected-(SW46-PadA)") (class "Default")
      (node (ref "SW46") (pin "A") (pinfunction "A_A") (pintype "bidirectional"))
    )
    (net (code "262") (name "unconnected-(SW46-PadK)") (class "Default")
      (node (ref "SW46") (pin "K") (pinfunction "K_K") (pintype "bidirectional"))
    )
    (net (code "263") (name "unconnected-(SW47-PadA)") (class "Default")
      (node (ref "SW47") (pin "A") (pinfunction "A_A") (pintype "bidirectional"))
    )
    (net (code "264") (name "unconnected-(SW47-PadK)") (class "Default")
      (node (ref "SW47") (pin "K") (pinfunction "K_K") (pintype "bidirectional"))
    )
    (net (code "265") (name "unconnected-(SW48-PadA)") (class "Default")
      (node (ref "SW48") (pin "A") (pinfunction "A_A") (pintype "bidirectional"))
    )
    (net (code "266") (name "unconnected-(SW48-PadK)") (class "Default")
      (node (ref "SW48") (pin "K") (pinfunction "K_K") (pintype "bidirectional"))
    )
    (net (code "267") (name "unconnected-(SW49-PadA)") (class "Default")
      (node (ref "SW49") (pin "A") (pinfunction "A_A") (pintype "bidirectional"))
    )
    (net (code "268") (name "unconnected-(SW49-PadK)") (class "Default")
      (node (ref "SW49") (pin "K") (pinfunction "K_K") (pintype "bidirectional"))
    )
    (net (code "269") (name "unconnected-(SW50-PadA)") (class "Default")
      (node (ref "SW50") (pin "A") (pinfunction "A_A") (pintype "bidirectional"))
    )
    (net (code "270") (name "unconnected-(SW50-PadK)") (class "Default")
      (node (ref "SW50") (pin "K") (pinfunction "K_K") (pintype "bidirectional"))
    )
    (net (code "271") (name "unconnected-(SW51-PadA)") (class "Default")
      (node (ref "SW51") (pin "A") (pinfunction "A_A") (pintype "bidirectional"))
    )
    (net (code "272") (name "unconnected-(SW51-PadK)") (class "Default")
      (node (ref "SW51") (pin "K") (pinfunction "K_K") (pintype "bidirectional"))
    )
    (net (code "273") (name "unconnected-(SW52-PadA)") (class "Default")
      (node (ref "SW52") (pin "A") (pinfunction "A_A") (pintype "bidirectional"))
    )
    (net (code "274") (name "unconnected-(SW52-PadK)") (class "Default")
      (node (ref "SW52") (pin "K") (pinfunction "K_K") (pintype "bidirectional"))
    )
    (net (code "275") (name "unconnected-(SW53-PadA)") (class "Default")
      (node (ref "SW53") (pin "A") (pinfunction "A_A") (pintype "bidirectional"))
    )
    (net (code "276") (name "unconnected-(SW53-PadK)") (class "Default")
      (node (ref "SW53") (pin "K") (pinfunction "K_K") (pintype "bidirectional"))
    )
    (net (code "277") (name "unconnected-(SW54-PadA)") (class "Default")
      (node (ref "SW54") (pin "A") (pinfunction "A_A") (pintype "bidirectional"))
    )
    (net (code "278") (name "unconnected-(SW54-PadK)") (class "Default")
      (node (ref "SW54") (pin "K") (pinfunction "K_K") (pintype "bidirectional"))
    )
    (net (code "279") (name "unconnected-(SW55-PadA)") (class "Default")
      (node (ref "SW55") (pin "A") (pinfunction "A_A") (pintype "bidirectional"))
    )
    (net (code "280") (name "unconnected-(SW55-PadK)") (class "Default")
      (node (ref "SW55") (pin "K") (pinfunction "K_K") (pintype "bidirectional"))
    )
    (net (code "281") (name "unconnected-(SW56-PadA)") (class "Default")
      (node (ref "SW56") (pin "A") (pinfunction "A_A") (pintype "bidirectional"))
    )
    (net (code "282") (name "unconnected-(SW56-PadK)") (class "Default")
      (node (ref "SW56") (pin "K") (pinfunction "K_K") (pintype "bidirectional"))
    )
    (net (code "283") (name "unconnected-(SW57-PadA)") (class "Default")
      (node (ref "SW57") (pin "A") (pinfunction "A_A") (pintype "bidirectional"))
    )
    (net (code "284") (name "unconnected-(SW57-PadK)") (class "Default")
      (node (ref "SW57") (pin "K") (pinfunction "K_K") (pintype "bidirectional"))
    )
    (net (code "285") (name "unconnected-(SW58-PadA)") (class "Default")
      (node (ref "SW58") (pin "A") (pinfunction "A_A") (pintype "bidirectional"))
    )
    (net (code "286") (name "unconnected-(SW58-PadK)") (class "Default")
      (node (ref "SW58") (pin "K") (pinfunction "K_K") (pintype "bidirectional"))
    )
    (net (code "287") (name "unconnected-(SW59-PadA)") (class "Default")
      (node (ref "SW59") (pin "A") (pinfunction "A_A") (pintype "bidirectional"))
    )
    (net (code "288") (name "unconnected-(SW59-PadK)") (class "Default")
      (node (ref "SW59") (pin "K") (pinfunction "K_K") (pintype "bidirectional"))
    )
    (net (code "289") (name "unconnected-(SW60-PadA)") (class "Default")
      (node (ref "SW60") (pin "A") (pinfunction "A_A") (pintype "bidirectional"))
    )
    (net (code "290") (name "unconnected-(SW60-PadK)") (class "Default")
      (node (ref "SW60") (pin "K") (pinfunction "K_K") (pintype "bidirectional"))
    )
    (net (code "291") (name "unconnected-(SW61-PadA)") (class "Default")
      (node (ref "SW61") (pin "A") (pinfunction "A_A") (pintype "bidirectional"))
    )
    (net (code "292") (name "unconnected-(SW61-PadK)") (class "Default")
      (node (ref "SW61") (pin "K") (pinfunction "K_K") (pintype "bidirectional"))
    )
    (net (code "293") (name "unconnected-(SW62-PadA)") (class "Default")
      (node (ref "SW62") (pin "A") (pinfunction "A_A") (pintype "bidirectional"))
    )
    (net (code "294") (name "unconnected-(SW62-PadK)") (class "Default")
      (node (ref "SW62") (pin "K") (pinfunction "K_K") (pintype "bidirectional"))
    )
    (net (code "295") (name "unconnected-(SW63-PadA)") (class "Default")
      (node (ref "SW63") (pin "A") (pinfunction "A_A") (pintype "bidirectional"))
    )
    (net (code "296") (name "unconnected-(SW63-PadK)") (class "Default")
      (node (ref "SW63") (pin "K") (pinfunction "K_K") (pintype "bidirectional"))
    )
    (net (code "297") (name "unconnected-(SW64-PadA)") (class "Default")
      (node (ref "SW64") (pin "A") (pinfunction "A_A") (pintype "bidirectional"))
    )
    (net (code "298") (name "unconnected-(SW64-PadK)") (class "Default")
      (node (ref "SW64") (pin "K") (pinfunction "K_K") (pintype "bidirectional"))
    )
    (net (code "299") (name "unconnected-(SW65-PadA)") (class "Default")
      (node (ref "SW65") (pin "A") (pinfunction "A_A") (pintype "bidirectional"))
    )
    (net (code "300") (name "unconnected-(SW65-PadK)") (class "Default")
      (node (ref "SW65") (pin "K") (pinfunction "K_K") (pintype "bidirectional"))
    )
    (net (code "301") (name "unconnected-(SW66-PadA)") (class "Default")
      (node (ref "SW66") (pin "A") (pinfunction "A_A") (pintype "bidirectional"))
    )
    (net (code "302") (name "unconnected-(SW66-PadK)") (class "Default")
      (node (ref "SW66") (pin "K") (pinfunction "K_K") (pintype "bidirectional"))
    )
    (net (code "303") (name "unconnected-(SW67-PadA)") (class "Default")
      (node (ref "SW67") (pin "A") (pinfunction "A_A") (pintype "bidirectional"))
    )
    (net (code "304") (name "unconnected-(SW67-PadK)") (class "Default")
      (node (ref "SW67") (pin "K") (pinfunction "K_K") (pintype "bidirectional"))
    )
    (net (code "305") (name "unconnected-(SW68-PadA)") (class "Default")
      (node (ref "SW68") (pin "A") (pinfunction "A_A") (pintype "bidirectional"))
    )
    (net (code "306") (name "unconnected-(SW68-PadK)") (class "Default")
      (node (ref "SW68") (pin "K") (pinfunction "K_K") (pintype "bidirectional"))
    )
    (net (code "307") (name "unconnected-(SW69-PadA)") (class "Default")
      (node (ref "SW69") (pin "A") (pinfunction "A_A") (pintype "bidirectional"))
    )
    (net (code "308") (name "unconnected-(SW69-PadK)") (class "Default")
      (node (ref "SW69") (pin "K") (pinfunction "K_K") (pintype "bidirectional"))
    )
    (net (code "309") (name "unconnected-(SW70-PadA)") (class "Default")
      (node (ref "SW70") (pin "A") (pinfunction "A_A") (pintype "bidirectional"))
    )
    (net (code "310") (name "unconnected-(SW70-PadK)") (class "Default")
      (node (ref "SW70") (pin "K") (pinfunction "K_K") (pintype "bidirectional"))
    )
    (net (code "311") (name "unconnected-(SW71-PadA)") (class "Default")
      (node (ref "SW71") (pin "A") (pinfunction "A_A") (pintype "bidirectional"))
    )
    (net (code "312") (name "unconnected-(SW71-PadK)") (class "Default")
      (node (ref "SW71") (pin "K") (pinfunction "K_K") (pintype "bidirectional"))
    )
    (net (code "313") (name "unconnected-(SW72-PadA)") (class "Default")
      (node (ref "SW72") (pin "A") (pinfunction "A_A") (pintype "bidirectional"))
    )
    (net (code "314") (name "unconnected-(SW72-PadK)") (class "Default")
      (node (ref "SW72") (pin "K") (pinfunction "K_K") (pintype "bidirectional"))
    )
    (net (code "315") (name "unconnected-(SW73-PadA)") (class "Default")
      (node (ref "SW73") (pin "A") (pinfunction "A_A") (pintype "bidirectional"))
    )
    (net (code "316") (name "unconnected-(SW73-PadK)") (class "Default")
      (node (ref "SW73") (pin "K") (pinfunction "K_K") (pintype "bidirectional"))
    )
    (net (code "317") (name "unconnected-(SW74-PadA)") (class "Default")
      (node (ref "SW74") (pin "A") (pinfunction "A_A") (pintype "bidirectional"))
    )
    (net (code "318") (name "unconnected-(SW74-PadK)") (class "Default")
      (node (ref "SW74") (pin "K") (pinfunction "K_K") (pintype "bidirectional"))
    )
    (net (code "319") (name "unconnected-(SW75-PadA)") (class "Default")
      (node (ref "SW75") (pin "A") (pinfunction "A_A") (pintype "bidirectional"))
    )
    (net (code "320") (name "unconnected-(SW75-PadK)") (class "Default")
      (node (ref "SW75") (pin "K") (pinfunction "K_K") (pintype "bidirectional"))
    )
    (net (code "321") (name "unconnected-(SW76-PadA)") (class "Default")
      (node (ref "SW76") (pin "A") (pinfunction "A_A") (pintype "bidirectional"))
    )
    (net (code "322") (name "unconnected-(SW76-PadK)") (class "Default")
      (node (ref "SW76") (pin "K") (pinfunction "K_K") (pintype "bidirectional"))
    )
    (net (code "323") (name "unconnected-(SW77-PadA)") (class "Default")
      (node (ref "SW77") (pin "A") (pinfunction "A_A") (pintype "bidirectional"))
    )
    (net (code "324") (name "unconnected-(SW77-PadK)") (class "Default")
      (node (ref "SW77") (pin "K") (pinfunction "K_K") (pintype "bidirectional"))
    )
    (net (code "325") (name "unconnected-(SW78-PadA)") (class "Default")
      (node (ref "SW78") (pin "A") (pinfunction "A_A") (pintype "bidirectional"))
    )
    (net (code "326") (name "unconnected-(SW78-PadK)") (class "Default")
      (node (ref "SW78") (pin "K") (pinfunction "K_K") (pintype "bidirectional"))
    )
    (net (code "327") (name "unconnected-(SW79-PadA)") (class "Default")
      (node (ref "SW79") (pin "A") (pinfunction "A_A") (pintype "bidirectional"))
    )
    (net (code "328") (name "unconnected-(SW79-PadK)") (class "Default")
      (node (ref "SW79") (pin "K") (pinfunction "K_K") (pintype "bidirectional"))
    )
    (net (code "329") (name "unconnected-(SW80-PadA)") (class "Default")
      (node (ref "SW80") (pin "A") (pinfunction "A_A") (pintype "bidirectional"))
    )
    (net (code "330") (name "unconnected-(SW80-PadK)") (class "Default")
      (node (ref "SW80") (pin "K") (pinfunction "K_K") (pintype "bidirectional"))
    )
    (net (code "331") (name "unconnected-(SW81-PadA)") (class "Default")
      (node (ref "SW81") (pin "A") (pinfunction "A_A") (pintype "bidirectional"))
    )
    (net (code "332") (name "unconnected-(SW81-PadK)") (class "Default")
      (node (ref "SW81") (pin "K") (pinfunction "K_K") (pintype "bidirectional"))
    )
    (net (code "333") (name "unconnected-(SW82-PadA)") (class "Default")
      (node (ref "SW82") (pin "A") (pinfunction "A_A") (pintype "bidirectional"))
    )
    (net (code "334") (name "unconnected-(SW82-PadK)") (class "Default")
      (node (ref "SW82") (pin "K") (pinfunction "K_K") (pintype "bidirectional"))
    )
    (net (code "335") (name "unconnected-(SW83-PadA)") (class "Default")
      (node (ref "SW83") (pin "A") (pinfunction "A_A") (pintype "bidirectional"))
    )
    (net (code "336") (name "unconnected-(SW83-PadK)") (class "Default")
      (node (ref "SW83") (pin "K") (pinfunction "K_K") (pintype "bidirectional"))
    )
    (net (code "337") (name "unconnected-(SW84-PadA)") (class "Default")
      (node (ref "SW84") (pin "A") (pinfunction "A_A") (pintype "bidirectional"))
    )
    (net (code "338") (name "unconnected-(SW84-PadK)") (class "Default")
      (node (ref "SW84") (pin "K") (pinfunction "K_K") (pintype "bidirectional"))
    )
    (net (code "339") (name "unconnected-(SW86-PadA)") (class "Default")
      (node (ref "SW86") (pin "A") (pinfunction "A_A") (pintype "bidirectional"))
    )
    (net (code "340") (name "unconnected-(SW86-PadK)") (class "Default")
      (node (ref "SW86") (pin "K") (pinfunction "K_K") (pintype "bidirectional"))
    )
    (net (code "341") (name "unconnected-(SW87-PadA)") (class "Default")
      (node (ref "SW87") (pin "A") (pinfunction "A_A") (pintype "bidirectional"))
    )
    (net (code "342") (name "unconnected-(SW87-PadK)") (class "Default")
      (node (ref "SW87") (pin "K") (pinfunction "K_K") (pintype "bidirectional"))
    )
    (net (code "343") (name "unconnected-(SW88-PadA)") (class "Default")
      (node (ref "SW88") (pin "A") (pinfunction "A_A") (pintype "bidirectional"))
    )
    (net (code "344") (name "unconnected-(SW88-PadK)") (class "Default")
      (node (ref "SW88") (pin "K") (pinfunction "K_K") (pintype "bidirectional"))
    )
    (net (code "345") (name "unconnected-(SW89-PadA)") (class "Default")
      (node (ref "SW89") (pin "A") (pinfunction "A_A") (pintype "bidirectional"))
    )
    (net (code "346") (name "unconnected-(SW89-PadK)") (class "Default")
      (node (ref "SW89") (pin "K") (pinfunction "K_K") (pintype "bidirectional"))
    )
    (net (code "347") (name "unconnected-(SW90-PadA)") (class "Default")
      (node (ref "SW90") (pin "A") (pinfunction "A_A") (pintype "bidirectional"))
    )
    (net (code "348") (name "unconnected-(SW90-PadK)") (class "Default")
      (node (ref "SW90") (pin "K") (pinfunction "K_K") (pintype "bidirectional"))
    )
    (net (code "349") (name "unconnected-(SW91-PadA)") (class "Default")
      (node (ref "SW91") (pin "A") (pinfunction "A_A") (pintype "bidirectional"))
    )
    (net (code "350") (name "unconnected-(SW91-PadK)") (class "Default")
      (node (ref "SW91") (pin "K") (pinfunction "K_K") (pintype "bidirectional"))
    )
    (net (code "351") (name "unconnected-(SW92-PadA)") (class "Default")
      (node (ref "SW92") (pin "A") (pinfunction "A_A") (pintype "bidirectional"))
    )
    (net (code "352") (name "unconnected-(SW92-PadK)") (class "Default")
      (node (ref "SW92") (pin "K") (pinfunction "K_K") (pintype "bidirectional"))
    )
  )
)
